# MCU.net
KiCad netlist of a schematic drawn in Altium Designer
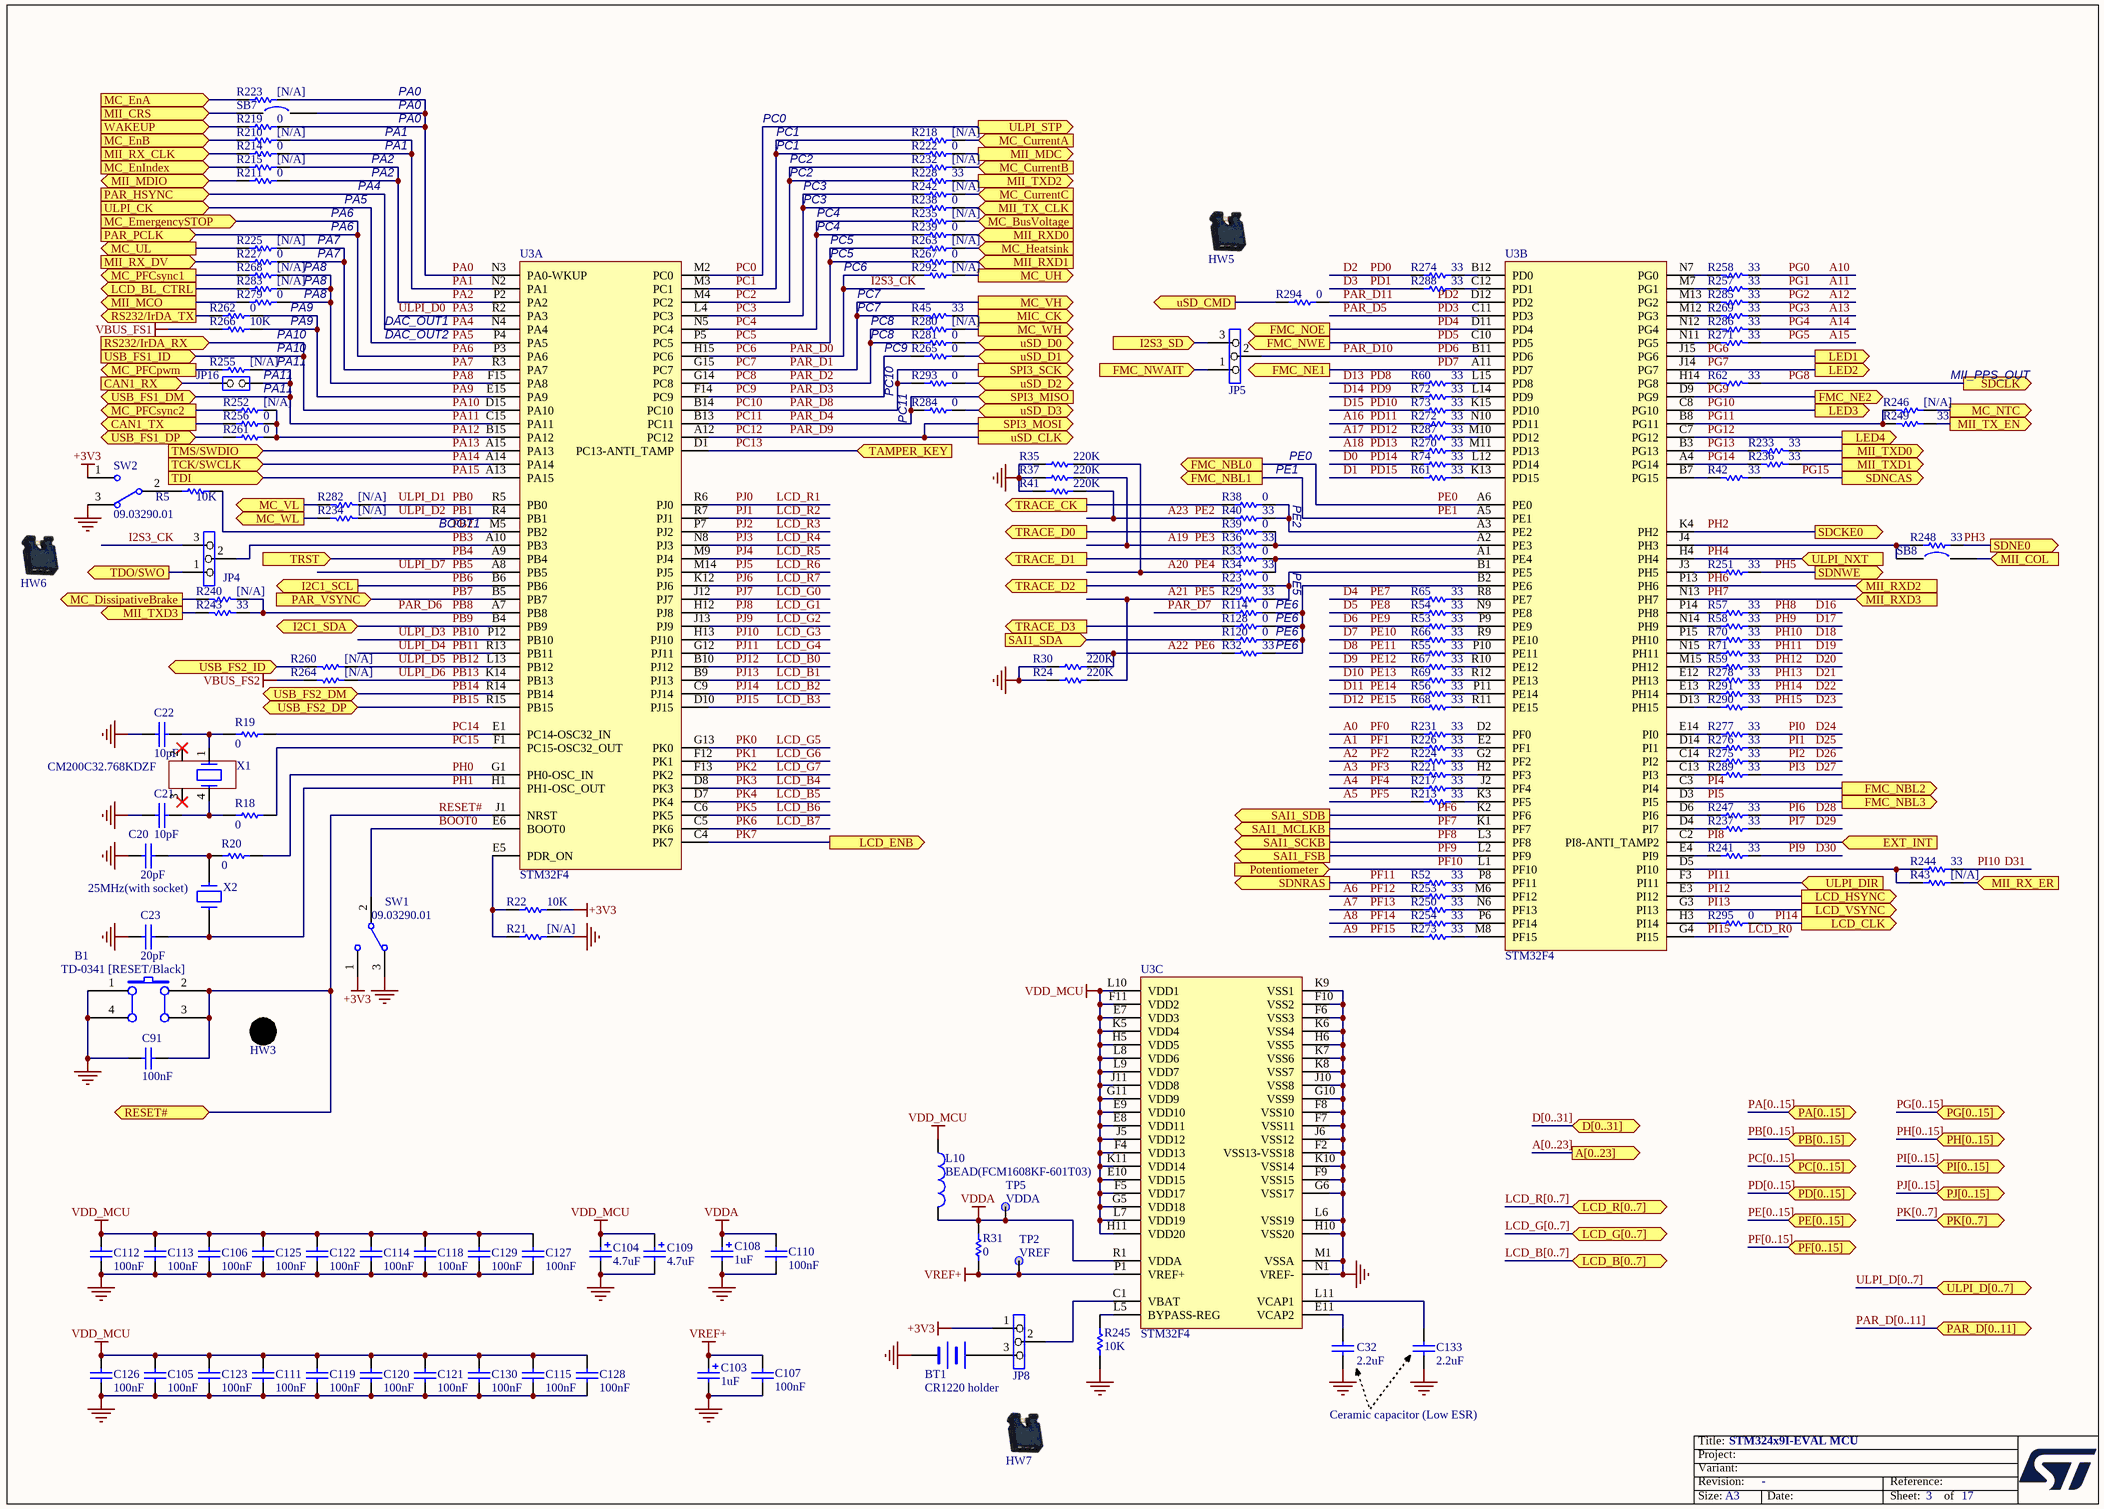
[diagram p0: MCU.SchDoc]

(export (version "E")
  (design (tool "Eeschema 10.0.6"))
  (components
    (comp (ref "B1")
      (value "TD-0341 [RESET/Black]")
      (footprint "PB10")
      (description "SE PUSHBUTTON")
      (libsource (lib "Documents") (part "SW PUSHBUTTON"))
    )
    (comp (ref "BT1")
      (value "CR1220 holder")
      (footprint "BAT_2SM_CR1220")
      (description "Battery")
      (libsource (lib "*") (part "BATTERY"))
    )
    (comp (ref "C20")
      (value "20pF")
      (footprint "0603C")
      (description "Capacitor")
      (libsource (lib "") (part "CAP_1"))
    )
    (comp (ref "C21")
      (value "10pF")
      (footprint "0603C")
      (description "Capacitor")
      (libsource (lib "*") (part "CAP"))
    )
    (comp (ref "C22")
      (value "10pF")
      (footprint "0603C")
      (description "Capacitor")
      (libsource (lib "*") (part "CAP"))
    )
    (comp (ref "C23")
      (value "20pF")
      (footprint "0603C")
      (description "Capacitor")
      (libsource (lib "") (part "CAP_1"))
    )
    (comp (ref "C32")
      (value "2.2uF")
      (footprint "1206C")
      (description "Capacitor")
      (fields (field (name "PUBLISHER") "Altium Limited"))
      (libsource (lib "Miscellaneous Devices") (part "Cap"))
    )
    (comp (ref "C91")
      (value "100nF")
      (footprint "0603C")
      (description "Capacitor")
      (fields (field (name "PUBLISHER") "Altium Limited"))
      (libsource (lib "Miscellaneous Devices") (part "CAP"))
    )
    (comp (ref "C103")
      (value "1uF")
      (footprint "TAN-A")
      (description "Polarized Capacitor (Radial)")
      (fields (field (name "PUBLISHER") "Altium Limited"))
      (libsource (lib "Miscellaneous Devices") (part "Cap Pol1"))
    )
    (comp (ref "C104")
      (value "4.7uF")
      (footprint "TAN-A")
      (description "Polarized Capacitor (Radial)")
      (fields (field (name "PUBLISHER") "Altium Limited"))
      (libsource (lib "Miscellaneous Devices") (part "Cap Pol1"))
    )
    (comp (ref "C105")
      (value "100nF")
      (footprint "0402C")
      (description "Capacitor")
      (fields (field (name "PUBLISHER") "Altium Limited"))
      (libsource (lib "Miscellaneous Devices") (part "CAP"))
    )
    (comp (ref "C106")
      (value "100nF")
      (footprint "0402C")
      (description "Capacitor")
      (fields (field (name "PUBLISHER") "Altium Limited"))
      (libsource (lib "Miscellaneous Devices") (part "CAP"))
    )
    (comp (ref "C107")
      (value "100nF")
      (footprint "0402C")
      (description "Capacitor")
      (fields (field (name "PUBLISHER") "Altium Limited"))
      (libsource (lib "Miscellaneous Devices") (part "Cap"))
    )
    (comp (ref "C108")
      (value "1uF")
      (footprint "TAN-A")
      (description "Polarized Capacitor (Radial)")
      (fields (field (name "PUBLISHER") "Altium Limited"))
      (libsource (lib "Miscellaneous Devices") (part "Cap Pol1"))
    )
    (comp (ref "C109")
      (value "4.7uF")
      (footprint "TAN-A")
      (description "Polarized Capacitor (Radial)")
      (fields (field (name "PUBLISHER") "Altium Limited"))
      (libsource (lib "Miscellaneous Devices") (part "Cap Pol1"))
    )
    (comp (ref "C110")
      (value "100nF")
      (footprint "0402C")
      (description "Capacitor")
      (fields (field (name "PUBLISHER") "Altium Limited"))
      (libsource (lib "Miscellaneous Devices") (part "Cap"))
    )
    (comp (ref "C111")
      (value "100nF")
      (footprint "0402C")
      (description "Capacitor")
      (fields (field (name "PUBLISHER") "Altium Limited"))
      (libsource (lib "Miscellaneous Devices") (part "CAP"))
    )
    (comp (ref "C112")
      (value "100nF")
      (footprint "0402C")
      (description "Capacitor")
      (fields (field (name "PUBLISHER") "Altium Limited"))
      (libsource (lib "Miscellaneous Devices") (part "CAP"))
    )
    (comp (ref "C113")
      (value "100nF")
      (footprint "0402C")
      (description "Capacitor")
      (fields (field (name "PUBLISHER") "Altium Limited"))
      (libsource (lib "Miscellaneous Devices") (part "CAP"))
    )
    (comp (ref "C114")
      (value "100nF")
      (footprint "0402C")
      (description "Capacitor")
      (fields (field (name "PUBLISHER") "Altium Limited"))
      (libsource (lib "Miscellaneous Devices") (part "CAP"))
    )
    (comp (ref "C115")
      (value "100nF")
      (footprint "0402C")
      (description "Capacitor")
      (fields (field (name "PUBLISHER") "Altium Limited"))
      (libsource (lib "Miscellaneous Devices") (part "CAP"))
    )
    (comp (ref "C118")
      (value "100nF")
      (footprint "0402C")
      (description "Capacitor")
      (fields (field (name "PUBLISHER") "Altium Limited"))
      (libsource (lib "Miscellaneous Devices") (part "CAP"))
    )
    (comp (ref "C119")
      (value "100nF")
      (footprint "0402C")
      (description "Capacitor")
      (fields (field (name "PUBLISHER") "Altium Limited"))
      (libsource (lib "Miscellaneous Devices") (part "CAP"))
    )
    (comp (ref "C120")
      (value "100nF")
      (footprint "0402C")
      (description "Capacitor")
      (fields (field (name "PUBLISHER") "Altium Limited"))
      (libsource (lib "Miscellaneous Devices") (part "CAP"))
    )
    (comp (ref "C121")
      (value "100nF")
      (footprint "0402C")
      (description "Capacitor")
      (fields (field (name "PUBLISHER") "Altium Limited"))
      (libsource (lib "Miscellaneous Devices") (part "CAP"))
    )
    (comp (ref "C122")
      (value "100nF")
      (footprint "0402C")
      (description "Capacitor")
      (fields (field (name "PUBLISHER") "Altium Limited"))
      (libsource (lib "Miscellaneous Devices") (part "CAP"))
    )
    (comp (ref "C123")
      (value "100nF")
      (footprint "0402C")
      (description "Capacitor")
      (fields (field (name "PUBLISHER") "Altium Limited"))
      (libsource (lib "Miscellaneous Devices") (part "CAP"))
    )
    (comp (ref "C125")
      (value "100nF")
      (footprint "0402C")
      (description "Capacitor")
      (fields (field (name "PUBLISHER") "Altium Limited"))
      (libsource (lib "Miscellaneous Devices") (part "CAP"))
    )
    (comp (ref "C126")
      (value "100nF")
      (footprint "0402C")
      (description "Capacitor")
      (fields (field (name "PUBLISHER") "Altium Limited"))
      (libsource (lib "Miscellaneous Devices") (part "CAP"))
    )
    (comp (ref "C127")
      (value "100nF")
      (footprint "0402C")
      (description "Capacitor")
      (fields (field (name "PUBLISHER") "Altium Limited"))
      (libsource (lib "Miscellaneous Devices") (part "CAP"))
    )
    (comp (ref "C128")
      (value "100nF")
      (footprint "0402C")
      (description "Capacitor")
      (fields (field (name "PUBLISHER") "Altium Limited"))
      (libsource (lib "Miscellaneous Devices") (part "CAP"))
    )
    (comp (ref "C129")
      (value "100nF")
      (footprint "0402C")
      (description "Capacitor")
      (fields (field (name "PUBLISHER") "Altium Limited"))
      (libsource (lib "Miscellaneous Devices") (part "CAP"))
    )
    (comp (ref "C130")
      (value "100nF")
      (footprint "0402C")
      (description "Capacitor")
      (fields (field (name "PUBLISHER") "Altium Limited"))
      (libsource (lib "Miscellaneous Devices") (part "CAP"))
    )
    (comp (ref "C133")
      (value "2.2uF")
      (footprint "1206C")
      (description "Capacitor")
      (fields (field (name "PUBLISHER") "Altium Limited"))
      (libsource (lib "Miscellaneous Devices") (part "Cap"))
    )
    (comp (ref "HW3") (value "BUTTON_HAT_BLACK") (libsource (lib "mb1045") (part "BUTTON_HAT_BLACK")))
    (comp (ref "HW5") (value "JUMPER_OPEN") (libsource (lib "mb1045") (part "JUMPER_OPEN")))
    (comp (ref "HW6") (value "JUMPER_OPEN") (libsource (lib "mb1045") (part "JUMPER_OPEN")))
    (comp (ref "HW7") (value "JUMPER_OPEN") (libsource (lib "mb1045") (part "JUMPER_OPEN")))
    (comp (ref "JP4") (value "~") (footprint "SIP3") (libsource (lib "") (part "Jumper3_1")))
    (comp (ref "JP5") (value "~") (footprint "SIP3") (libsource (lib "") (part "Jumper3_1")))
    (comp (ref "JP8") (value "~") (footprint "SIP3") (libsource (lib "STR910_SCHLIB") (part "Jumper3")))
    (comp (ref "JP16") (value "~") (footprint "SIP2") (libsource (lib "*") (part "JP2")))
    (comp (ref "L10")
      (value "BEAD(FCM1608KF-601T03)")
      (footprint "0603L")
      (description "Inductor")
      (fields (field (name "PUBLISHER") "Altium Limited"))
      (libsource (lib "Miscellaneous Devices") (part "Inductor"))
    )
    (comp (ref "R5")
      (value "10K")
      (footprint "0603R")
      (description "Resistor")
      (fields (field (name "PUBLISHER") "Altium Limited"))
      (libsource (lib "Miscellaneous Devices") (part "Res1"))
    )
    (comp (ref "R18")
      (value "0")
      (footprint "0603R")
      (description "Resistor")
      (fields (field (name "PUBLISHER") "Altium Limited"))
      (libsource (lib "") (part "Res1_1"))
    )
    (comp (ref "R19")
      (value "0")
      (footprint "0603R")
      (description "Resistor")
      (fields (field (name "PUBLISHER") "Altium Limited"))
      (libsource (lib "") (part "Res1_1"))
    )
    (comp (ref "R20")
      (value "0")
      (footprint "0603R")
      (description "Resistor")
      (fields (field (name "PUBLISHER") "Altium Limited"))
      (libsource (lib "Miscellaneous Devices") (part "Res1"))
    )
    (comp (ref "R21")
      (value "[N/A]")
      (footprint "0603R")
      (description "Resistor")
      (fields (field (name "PUBLISHER") "Altium Limited"))
      (libsource (lib "Miscellaneous Devices") (part "Res1"))
    )
    (comp (ref "R22")
      (value "10K")
      (footprint "0603R")
      (description "Resistor")
      (fields (field (name "PUBLISHER") "Altium Limited"))
      (libsource (lib "Miscellaneous Devices") (part "Res1"))
    )
    (comp (ref "R23")
      (value "0")
      (footprint "0603R")
      (description "Resistor")
      (fields (field (name "PUBLISHER") "Altium Limited"))
      (libsource (lib "Miscellaneous Devices") (part "Res1"))
    )
    (comp (ref "R24")
      (value "220K")
      (footprint "0603R")
      (description "Resistor")
      (fields (field (name "PUBLISHER") "Altium Limited"))
      (libsource (lib "Miscellaneous Devices") (part "res1"))
    )
    (comp (ref "R29")
      (value "33")
      (footprint "0402R")
      (description "Resistor")
      (fields (field (name "PUBLISHER") "Altium Limited"))
      (libsource (lib "Miscellaneous Devices") (part "Res1"))
    )
    (comp (ref "R30")
      (value "220K")
      (footprint "0603R")
      (description "Resistor")
      (fields (field (name "PUBLISHER") "Altium Limited"))
      (libsource (lib "Miscellaneous Devices") (part "res1"))
    )
    (comp (ref "R31")
      (value "0")
      (footprint "0603R")
      (description "Resistor")
      (fields (field (name "PUBLISHER") "Altium Limited"))
      (libsource (lib "Miscellaneous Devices") (part "Res1"))
    )
    (comp (ref "R32")
      (value "33")
      (footprint "0402R")
      (description "Resistor")
      (fields (field (name "PUBLISHER") "Altium Limited"))
      (libsource (lib "Miscellaneous Devices") (part "Res1"))
    )
    (comp (ref "R33")
      (value "0")
      (footprint "0603R")
      (description "Resistor")
      (fields (field (name "PUBLISHER") "Altium Limited"))
      (libsource (lib "Miscellaneous Devices") (part "Res1"))
    )
    (comp (ref "R34")
      (value "33")
      (footprint "0402R")
      (description "Resistor")
      (fields (field (name "PUBLISHER") "Altium Limited"))
      (libsource (lib "Miscellaneous Devices") (part "Res1"))
    )
    (comp (ref "R35")
      (value "220K")
      (footprint "0603R")
      (description "Resistor")
      (fields (field (name "PUBLISHER") "Altium Limited"))
      (libsource (lib "Miscellaneous Devices") (part "res1"))
    )
    (comp (ref "R36")
      (value "33")
      (footprint "0402R")
      (description "Resistor")
      (fields (field (name "PUBLISHER") "Altium Limited"))
      (libsource (lib "Miscellaneous Devices") (part "Res1"))
    )
    (comp (ref "R37")
      (value "220K")
      (footprint "0603R")
      (description "Resistor")
      (fields (field (name "PUBLISHER") "Altium Limited"))
      (libsource (lib "Miscellaneous Devices") (part "res1"))
    )
    (comp (ref "R38")
      (value "0")
      (footprint "0603R")
      (description "Resistor")
      (fields (field (name "PUBLISHER") "Altium Limited"))
      (libsource (lib "Miscellaneous Devices") (part "Res1"))
    )
    (comp (ref "R39")
      (value "0")
      (footprint "0603R")
      (description "Resistor")
      (fields (field (name "PUBLISHER") "Altium Limited"))
      (libsource (lib "Miscellaneous Devices") (part "Res1"))
    )
    (comp (ref "R40")
      (value "33")
      (footprint "0402R")
      (description "Resistor")
      (fields (field (name "PUBLISHER") "Altium Limited"))
      (libsource (lib "Miscellaneous Devices") (part "Res1"))
    )
    (comp (ref "R41")
      (value "220K")
      (footprint "0603R")
      (description "Resistor")
      (fields (field (name "PUBLISHER") "Altium Limited"))
      (libsource (lib "Miscellaneous Devices") (part "res1"))
    )
    (comp (ref "R42")
      (value "33")
      (footprint "0402R")
      (description "Resistor")
      (fields (field (name "PUBLISHER") "Altium Limited"))
      (libsource (lib "Miscellaneous Devices") (part "Res1"))
    )
    (comp (ref "R43")
      (value "[N/A]")
      (footprint "0603R")
      (description "Resistor")
      (fields (field (name "PUBLISHER") "Altium Limited"))
      (libsource (lib "Miscellaneous Devices") (part "Res1"))
    )
    (comp (ref "R45")
      (value "33")
      (footprint "0603R")
      (description "Resistor")
      (fields (field (name "PUBLISHER") "Altium Limited"))
      (libsource (lib "Miscellaneous Devices") (part "Res1"))
    )
    (comp (ref "R52")
      (value "33")
      (footprint "0402R")
      (description "Resistor")
      (fields (field (name "PUBLISHER") "Altium Limited"))
      (libsource (lib "Miscellaneous Devices") (part "Res1"))
    )
    (comp (ref "R53")
      (value "33")
      (footprint "0402R")
      (description "Resistor")
      (fields (field (name "PUBLISHER") "Altium Limited"))
      (libsource (lib "Miscellaneous Devices") (part "Res1"))
    )
    (comp (ref "R54")
      (value "33")
      (footprint "0402R")
      (description "Resistor")
      (fields (field (name "PUBLISHER") "Altium Limited"))
      (libsource (lib "Miscellaneous Devices") (part "Res1"))
    )
    (comp (ref "R55")
      (value "33")
      (footprint "0402R")
      (description "Resistor")
      (fields (field (name "PUBLISHER") "Altium Limited"))
      (libsource (lib "Miscellaneous Devices") (part "Res1"))
    )
    (comp (ref "R56")
      (value "33")
      (footprint "0402R")
      (description "Resistor")
      (fields (field (name "PUBLISHER") "Altium Limited"))
      (libsource (lib "Miscellaneous Devices") (part "Res1"))
    )
    (comp (ref "R57")
      (value "33")
      (footprint "0402R")
      (description "Resistor")
      (fields (field (name "PUBLISHER") "Altium Limited"))
      (libsource (lib "Miscellaneous Devices") (part "Res1"))
    )
    (comp (ref "R58")
      (value "33")
      (footprint "0402R")
      (description "Resistor")
      (fields (field (name "PUBLISHER") "Altium Limited"))
      (libsource (lib "Miscellaneous Devices") (part "Res1"))
    )
    (comp (ref "R59")
      (value "33")
      (footprint "0402R")
      (description "Resistor")
      (fields (field (name "PUBLISHER") "Altium Limited"))
      (libsource (lib "Miscellaneous Devices") (part "Res1"))
    )
    (comp (ref "R60")
      (value "33")
      (footprint "0402R")
      (description "Resistor")
      (fields (field (name "PUBLISHER") "Altium Limited"))
      (libsource (lib "Miscellaneous Devices") (part "Res1"))
    )
    (comp (ref "R61")
      (value "33")
      (footprint "0402R")
      (description "Resistor")
      (fields (field (name "PUBLISHER") "Altium Limited"))
      (libsource (lib "Miscellaneous Devices") (part "Res1"))
    )
    (comp (ref "R62")
      (value "33")
      (footprint "0402R")
      (description "Resistor")
      (fields (field (name "PUBLISHER") "Altium Limited"))
      (libsource (lib "Miscellaneous Devices") (part "Res1"))
    )
    (comp (ref "R65")
      (value "33")
      (footprint "0402R")
      (description "Resistor")
      (fields (field (name "PUBLISHER") "Altium Limited"))
      (libsource (lib "Miscellaneous Devices") (part "Res1"))
    )
    (comp (ref "R66")
      (value "33")
      (footprint "0402R")
      (description "Resistor")
      (fields (field (name "PUBLISHER") "Altium Limited"))
      (libsource (lib "Miscellaneous Devices") (part "Res1"))
    )
    (comp (ref "R67")
      (value "33")
      (footprint "0402R")
      (description "Resistor")
      (fields (field (name "PUBLISHER") "Altium Limited"))
      (libsource (lib "Miscellaneous Devices") (part "Res1"))
    )
    (comp (ref "R68")
      (value "33")
      (footprint "0402R")
      (description "Resistor")
      (fields (field (name "PUBLISHER") "Altium Limited"))
      (libsource (lib "Miscellaneous Devices") (part "Res1"))
    )
    (comp (ref "R69")
      (value "33")
      (footprint "0402R")
      (description "Resistor")
      (fields (field (name "PUBLISHER") "Altium Limited"))
      (libsource (lib "Miscellaneous Devices") (part "Res1"))
    )
    (comp (ref "R70")
      (value "33")
      (footprint "0402R")
      (description "Resistor")
      (fields (field (name "PUBLISHER") "Altium Limited"))
      (libsource (lib "Miscellaneous Devices") (part "Res1"))
    )
    (comp (ref "R71")
      (value "33")
      (footprint "0402R")
      (description "Resistor")
      (fields (field (name "PUBLISHER") "Altium Limited"))
      (libsource (lib "Miscellaneous Devices") (part "Res1"))
    )
    (comp (ref "R72")
      (value "33")
      (footprint "0402R")
      (description "Resistor")
      (fields (field (name "PUBLISHER") "Altium Limited"))
      (libsource (lib "Miscellaneous Devices") (part "Res1"))
    )
    (comp (ref "R73")
      (value "33")
      (footprint "0402R")
      (description "Resistor")
      (fields (field (name "PUBLISHER") "Altium Limited"))
      (libsource (lib "Miscellaneous Devices") (part "Res1"))
    )
    (comp (ref "R74")
      (value "33")
      (footprint "0402R")
      (description "Resistor")
      (fields (field (name "PUBLISHER") "Altium Limited"))
      (libsource (lib "Miscellaneous Devices") (part "Res1"))
    )
    (comp (ref "R114")
      (value "0")
      (footprint "0603R")
      (description "Resistor")
      (fields (field (name "PUBLISHER") "Altium Limited"))
      (libsource (lib "Miscellaneous Devices") (part "Res1"))
    )
    (comp (ref "R120")
      (value "0")
      (footprint "0603R")
      (description "Resistor")
      (fields (field (name "PUBLISHER") "Altium Limited"))
      (libsource (lib "Miscellaneous Devices") (part "Res1"))
    )
    (comp (ref "R128")
      (value "0")
      (footprint "0603R")
      (description "Resistor")
      (fields (field (name "PUBLISHER") "Altium Limited"))
      (libsource (lib "Miscellaneous Devices") (part "Res1"))
    )
    (comp (ref "R210")
      (value "[N/A]")
      (footprint "0603R")
      (description "Resistor")
      (fields (field (name "PUBLISHER") "Altium Limited"))
      (libsource (lib "Miscellaneous Devices") (part "Res1"))
    )
    (comp (ref "R211")
      (value "0")
      (footprint "0603R")
      (description "Resistor")
      (fields (field (name "PUBLISHER") "Altium Limited"))
      (libsource (lib "Miscellaneous Devices") (part "Res1"))
    )
    (comp (ref "R213")
      (value "33")
      (footprint "0402R")
      (description "Resistor")
      (fields (field (name "PUBLISHER") "Altium Limited"))
      (libsource (lib "Miscellaneous Devices") (part "Res1"))
    )
    (comp (ref "R214")
      (value "0")
      (footprint "0603R")
      (description "Resistor")
      (fields (field (name "PUBLISHER") "Altium Limited"))
      (libsource (lib "Miscellaneous Devices") (part "Res1"))
    )
    (comp (ref "R215")
      (value "[N/A]")
      (footprint "0603R")
      (description "Resistor")
      (fields (field (name "PUBLISHER") "Altium Limited"))
      (libsource (lib "Miscellaneous Devices") (part "Res1"))
    )
    (comp (ref "R217")
      (value "33")
      (footprint "0402R")
      (description "Resistor")
      (fields (field (name "PUBLISHER") "Altium Limited"))
      (libsource (lib "Miscellaneous Devices") (part "Res1"))
    )
    (comp (ref "R218")
      (value "[N/A]")
      (footprint "0603R")
      (description "Resistor")
      (fields (field (name "PUBLISHER") "Altium Limited"))
      (libsource (lib "Miscellaneous Devices") (part "Res1"))
    )
    (comp (ref "R219")
      (value "0")
      (footprint "0603R")
      (description "Resistor")
      (fields (field (name "PUBLISHER") "Altium Limited"))
      (libsource (lib "Miscellaneous Devices") (part "Res1"))
    )
    (comp (ref "R221")
      (value "33")
      (footprint "0402R")
      (description "Resistor")
      (fields (field (name "PUBLISHER") "Altium Limited"))
      (libsource (lib "Miscellaneous Devices") (part "Res1"))
    )
    (comp (ref "R222")
      (value "0")
      (footprint "0603R")
      (description "Resistor")
      (fields (field (name "PUBLISHER") "Altium Limited"))
      (libsource (lib "Miscellaneous Devices") (part "Res1"))
    )
    (comp (ref "R223")
      (value "[N/A]")
      (footprint "0603R")
      (description "Resistor")
      (fields (field (name "PUBLISHER") "Altium Limited"))
      (libsource (lib "Miscellaneous Devices") (part "Res1"))
    )
    (comp (ref "R224")
      (value "33")
      (footprint "0402R")
      (description "Resistor")
      (fields (field (name "PUBLISHER") "Altium Limited"))
      (libsource (lib "Miscellaneous Devices") (part "Res1"))
    )
    (comp (ref "R225")
      (value "[N/A]")
      (footprint "0603R")
      (description "Resistor")
      (fields (field (name "PUBLISHER") "Altium Limited"))
      (libsource (lib "Miscellaneous Devices") (part "Res1"))
    )
    (comp (ref "R226")
      (value "33")
      (footprint "0402R")
      (description "Resistor")
      (fields (field (name "PUBLISHER") "Altium Limited"))
      (libsource (lib "Miscellaneous Devices") (part "Res1"))
    )
    (comp (ref "R227")
      (value "0")
      (footprint "0603R")
      (description "Resistor")
      (fields (field (name "PUBLISHER") "Altium Limited"))
      (libsource (lib "Miscellaneous Devices") (part "Res1"))
    )
    (comp (ref "R228")
      (value "33")
      (footprint "0603R")
      (description "Resistor")
      (fields (field (name "PUBLISHER") "Altium Limited"))
      (libsource (lib "Miscellaneous Devices") (part "Res1"))
    )
    (comp (ref "R231")
      (value "33")
      (footprint "0402R")
      (description "Resistor")
      (fields (field (name "PUBLISHER") "Altium Limited"))
      (libsource (lib "Miscellaneous Devices") (part "Res1"))
    )
    (comp (ref "R232")
      (value "[N/A]")
      (footprint "0603R")
      (description "Resistor")
      (fields (field (name "PUBLISHER") "Altium Limited"))
      (libsource (lib "Miscellaneous Devices") (part "Res1"))
    )
    (comp (ref "R233")
      (value "33")
      (footprint "0603R")
      (description "Resistor")
      (fields (field (name "PUBLISHER") "Altium Limited"))
      (libsource (lib "Miscellaneous Devices") (part "Res1"))
    )
    (comp (ref "R234")
      (value "[N/A]")
      (footprint "0603R")
      (description "Resistor")
      (fields (field (name "PUBLISHER") "Altium Limited"))
      (libsource (lib "Miscellaneous Devices") (part "Res1"))
    )
    (comp (ref "R235")
      (value "[N/A]")
      (footprint "0603R")
      (description "Resistor")
      (fields (field (name "PUBLISHER") "Altium Limited"))
      (libsource (lib "Miscellaneous Devices") (part "Res1"))
    )
    (comp (ref "R236")
      (value "33")
      (footprint "0603R")
      (description "Resistor")
      (fields (field (name "PUBLISHER") "Altium Limited"))
      (libsource (lib "Miscellaneous Devices") (part "Res1"))
    )
    (comp (ref "R237")
      (value "33")
      (footprint "0402R")
      (description "Resistor")
      (fields (field (name "PUBLISHER") "Altium Limited"))
      (libsource (lib "Miscellaneous Devices") (part "Res1"))
    )
    (comp (ref "R238")
      (value "0")
      (footprint "0603R")
      (description "Resistor")
      (fields (field (name "PUBLISHER") "Altium Limited"))
      (libsource (lib "Miscellaneous Devices") (part "Res1"))
    )
    (comp (ref "R239")
      (value "0")
      (footprint "0603R")
      (description "Resistor")
      (fields (field (name "PUBLISHER") "Altium Limited"))
      (libsource (lib "Miscellaneous Devices") (part "Res1"))
    )
    (comp (ref "R240")
      (value "[N/A]")
      (footprint "0603R")
      (description "Resistor")
      (fields (field (name "PUBLISHER") "Altium Limited"))
      (libsource (lib "Miscellaneous Devices") (part "Res1"))
    )
    (comp (ref "R241")
      (value "33")
      (footprint "0402R")
      (description "Resistor")
      (fields (field (name "PUBLISHER") "Altium Limited"))
      (libsource (lib "Miscellaneous Devices") (part "Res1"))
    )
    (comp (ref "R242")
      (value "[N/A]")
      (footprint "0603R")
      (description "Resistor")
      (fields (field (name "PUBLISHER") "Altium Limited"))
      (libsource (lib "Miscellaneous Devices") (part "Res1"))
    )
    (comp (ref "R243")
      (value "33")
      (footprint "0603R")
      (description "Resistor")
      (fields (field (name "PUBLISHER") "Altium Limited"))
      (libsource (lib "Miscellaneous Devices") (part "Res1"))
    )
    (comp (ref "R244")
      (value "33")
      (footprint "0402R")
      (description "Resistor")
      (fields (field (name "PUBLISHER") "Altium Limited"))
      (libsource (lib "Miscellaneous Devices") (part "Res1"))
    )
    (comp (ref "R245")
      (value "10K")
      (footprint "0603R")
      (description "Resistor")
      (fields (field (name "PUBLISHER") "Altium Limited"))
      (libsource (lib "Miscellaneous Devices") (part "Res1"))
    )
    (comp (ref "R246")
      (value "[N/A]")
      (footprint "0603R")
      (description "Resistor")
      (fields (field (name "PUBLISHER") "Altium Limited"))
      (libsource (lib "Miscellaneous Devices") (part "Res1"))
    )
    (comp (ref "R247")
      (value "33")
      (footprint "0402R")
      (description "Resistor")
      (fields (field (name "PUBLISHER") "Altium Limited"))
      (libsource (lib "Miscellaneous Devices") (part "Res1"))
    )
    (comp (ref "R248")
      (value "33")
      (footprint "0402R")
      (description "Resistor")
      (fields (field (name "PUBLISHER") "Altium Limited"))
      (libsource (lib "Miscellaneous Devices") (part "Res1"))
    )
    (comp (ref "R249")
      (value "33")
      (footprint "0603R")
      (description "Resistor")
      (fields (field (name "PUBLISHER") "Altium Limited"))
      (libsource (lib "Miscellaneous Devices") (part "Res1"))
    )
    (comp (ref "R250")
      (value "33")
      (footprint "0402R")
      (description "Resistor")
      (fields (field (name "PUBLISHER") "Altium Limited"))
      (libsource (lib "Miscellaneous Devices") (part "Res1"))
    )
    (comp (ref "R251")
      (value "33")
      (footprint "0402R")
      (description "Resistor")
      (fields (field (name "PUBLISHER") "Altium Limited"))
      (libsource (lib "Miscellaneous Devices") (part "Res1"))
    )
    (comp (ref "R252")
      (value "[N/A]")
      (footprint "0603R")
      (description "Resistor")
      (fields (field (name "PUBLISHER") "Altium Limited"))
      (libsource (lib "Miscellaneous Devices") (part "Res1"))
    )
    (comp (ref "R253")
      (value "33")
      (footprint "0402R")
      (description "Resistor")
      (fields (field (name "PUBLISHER") "Altium Limited"))
      (libsource (lib "Miscellaneous Devices") (part "Res1"))
    )
    (comp (ref "R254")
      (value "33")
      (footprint "0402R")
      (description "Resistor")
      (fields (field (name "PUBLISHER") "Altium Limited"))
      (libsource (lib "Miscellaneous Devices") (part "Res1"))
    )
    (comp (ref "R255")
      (value "[N/A]")
      (footprint "0603R")
      (description "Resistor")
      (fields (field (name "PUBLISHER") "Altium Limited"))
      (libsource (lib "Miscellaneous Devices") (part "Res1"))
    )
    (comp (ref "R256")
      (value "0")
      (footprint "0603R")
      (description "Resistor")
      (fields (field (name "PUBLISHER") "Altium Limited"))
      (libsource (lib "Miscellaneous Devices") (part "Res1"))
    )
    (comp (ref "R257")
      (value "33")
      (footprint "0402R")
      (description "Resistor")
      (fields (field (name "PUBLISHER") "Altium Limited"))
      (libsource (lib "Miscellaneous Devices") (part "Res1"))
    )
    (comp (ref "R258")
      (value "33")
      (footprint "0402R")
      (description "Resistor")
      (fields (field (name "PUBLISHER") "Altium Limited"))
      (libsource (lib "Miscellaneous Devices") (part "Res1"))
    )
    (comp (ref "R260")
      (value "[N/A]")
      (footprint "0603R")
      (description "Resistor")
      (fields (field (name "PUBLISHER") "Altium Limited"))
      (libsource (lib "Miscellaneous Devices") (part "Res1"))
    )
    (comp (ref "R261")
      (value "0")
      (footprint "0603R")
      (description "Resistor")
      (fields (field (name "PUBLISHER") "Altium Limited"))
      (libsource (lib "Miscellaneous Devices") (part "Res1"))
    )
    (comp (ref "R262")
      (value "0")
      (footprint "0603R")
      (description "Resistor")
      (fields (field (name "PUBLISHER") "Altium Limited"))
      (libsource (lib "Miscellaneous Devices") (part "Res1"))
    )
    (comp (ref "R263")
      (value "[N/A]")
      (footprint "0603R")
      (description "Resistor")
      (fields (field (name "PUBLISHER") "Altium Limited"))
      (libsource (lib "Miscellaneous Devices") (part "Res1"))
    )
    (comp (ref "R264")
      (value "[N/A]")
      (footprint "0603R")
      (description "Resistor")
      (fields (field (name "PUBLISHER") "Altium Limited"))
      (libsource (lib "Miscellaneous Devices") (part "Res1"))
    )
    (comp (ref "R265")
      (value "0")
      (footprint "0603R")
      (description "Resistor")
      (fields (field (name "PUBLISHER") "Altium Limited"))
      (libsource (lib "Miscellaneous Devices") (part "Res1"))
    )
    (comp (ref "R266")
      (value "10K")
      (footprint "0603R")
      (description "Resistor")
      (fields (field (name "PUBLISHER") "Altium Limited"))
      (libsource (lib "Miscellaneous Devices") (part "res1"))
    )
    (comp (ref "R267")
      (value "0")
      (footprint "0603R")
      (description "Resistor")
      (fields (field (name "PUBLISHER") "Altium Limited"))
      (libsource (lib "Miscellaneous Devices") (part "Res1"))
    )
    (comp (ref "R268")
      (value "[N/A]")
      (footprint "0603R")
      (description "Resistor")
      (fields (field (name "PUBLISHER") "Altium Limited"))
      (libsource (lib "Miscellaneous Devices") (part "Res1"))
    )
    (comp (ref "R269")
      (value "33")
      (footprint "0402R")
      (description "Resistor")
      (fields (field (name "PUBLISHER") "Altium Limited"))
      (libsource (lib "Miscellaneous Devices") (part "Res1"))
    )
    (comp (ref "R270")
      (value "33")
      (footprint "0402R")
      (description "Resistor")
      (fields (field (name "PUBLISHER") "Altium Limited"))
      (libsource (lib "Miscellaneous Devices") (part "Res1"))
    )
    (comp (ref "R271")
      (value "33")
      (footprint "0402R")
      (description "Resistor")
      (fields (field (name "PUBLISHER") "Altium Limited"))
      (libsource (lib "Miscellaneous Devices") (part "Res1"))
    )
    (comp (ref "R272")
      (value "33")
      (footprint "0402R")
      (description "Resistor")
      (fields (field (name "PUBLISHER") "Altium Limited"))
      (libsource (lib "Miscellaneous Devices") (part "Res1"))
    )
    (comp (ref "R273")
      (value "33")
      (footprint "0402R")
      (description "Resistor")
      (fields (field (name "PUBLISHER") "Altium Limited"))
      (libsource (lib "Miscellaneous Devices") (part "Res1"))
    )
    (comp (ref "R274")
      (value "33")
      (footprint "0402R")
      (description "Resistor")
      (fields (field (name "PUBLISHER") "Altium Limited"))
      (libsource (lib "Miscellaneous Devices") (part "Res1"))
    )
    (comp (ref "R275")
      (value "33")
      (footprint "0402R")
      (description "Resistor")
      (fields (field (name "PUBLISHER") "Altium Limited"))
      (libsource (lib "Miscellaneous Devices") (part "Res1"))
    )
    (comp (ref "R276")
      (value "33")
      (footprint "0402R")
      (description "Resistor")
      (fields (field (name "PUBLISHER") "Altium Limited"))
      (libsource (lib "Miscellaneous Devices") (part "Res1"))
    )
    (comp (ref "R277")
      (value "33")
      (footprint "0402R")
      (description "Resistor")
      (fields (field (name "PUBLISHER") "Altium Limited"))
      (libsource (lib "Miscellaneous Devices") (part "Res1"))
    )
    (comp (ref "R278")
      (value "33")
      (footprint "0402R")
      (description "Resistor")
      (fields (field (name "PUBLISHER") "Altium Limited"))
      (libsource (lib "Miscellaneous Devices") (part "Res1"))
    )
    (comp (ref "R279")
      (value "0")
      (footprint "0603R")
      (description "Resistor")
      (fields (field (name "PUBLISHER") "Altium Limited"))
      (libsource (lib "Miscellaneous Devices") (part "Res1"))
    )
    (comp (ref "R280")
      (value "[N/A]")
      (footprint "0603R")
      (description "Resistor")
      (fields (field (name "PUBLISHER") "Altium Limited"))
      (libsource (lib "Miscellaneous Devices") (part "Res1"))
    )
    (comp (ref "R281")
      (value "0")
      (footprint "0603R")
      (description "Resistor")
      (fields (field (name "PUBLISHER") "Altium Limited"))
      (libsource (lib "Miscellaneous Devices") (part "Res1"))
    )
    (comp (ref "R282")
      (value "[N/A]")
      (footprint "0603R")
      (description "Resistor")
      (fields (field (name "PUBLISHER") "Altium Limited"))
      (libsource (lib "Miscellaneous Devices") (part "Res1"))
    )
    (comp (ref "R283")
      (value "[N/A]")
      (footprint "0603R")
      (description "Resistor")
      (fields (field (name "PUBLISHER") "Altium Limited"))
      (libsource (lib "Miscellaneous Devices") (part "Res1"))
    )
    (comp (ref "R284")
      (value "0")
      (footprint "0603R")
      (description "Resistor")
      (fields (field (name "PUBLISHER") "Altium Limited"))
      (libsource (lib "Miscellaneous Devices") (part "Res1"))
    )
    (comp (ref "R285")
      (value "33")
      (footprint "0402R")
      (description "Resistor")
      (fields (field (name "PUBLISHER") "Altium Limited"))
      (libsource (lib "Miscellaneous Devices") (part "Res1"))
    )
    (comp (ref "R286")
      (value "33")
      (footprint "0402R")
      (description "Resistor")
      (fields (field (name "PUBLISHER") "Altium Limited"))
      (libsource (lib "Miscellaneous Devices") (part "Res1"))
    )
    (comp (ref "R287")
      (value "33")
      (footprint "0402R")
      (description "Resistor")
      (fields (field (name "PUBLISHER") "Altium Limited"))
      (libsource (lib "Miscellaneous Devices") (part "Res1"))
    )
    (comp (ref "R288")
      (value "33")
      (footprint "0402R")
      (description "Resistor")
      (fields (field (name "PUBLISHER") "Altium Limited"))
      (libsource (lib "Miscellaneous Devices") (part "Res1"))
    )
    (comp (ref "R289")
      (value "33")
      (footprint "0402R")
      (description "Resistor")
      (fields (field (name "PUBLISHER") "Altium Limited"))
      (libsource (lib "Miscellaneous Devices") (part "Res1"))
    )
    (comp (ref "R290")
      (value "33")
      (footprint "0402R")
      (description "Resistor")
      (fields (field (name "PUBLISHER") "Altium Limited"))
      (libsource (lib "Miscellaneous Devices") (part "Res1"))
    )
    (comp (ref "R291")
      (value "33")
      (footprint "0402R")
      (description "Resistor")
      (fields (field (name "PUBLISHER") "Altium Limited"))
      (libsource (lib "Miscellaneous Devices") (part "Res1"))
    )
    (comp (ref "R292")
      (value "[N/A]")
      (footprint "0603R")
      (description "Resistor")
      (fields (field (name "PUBLISHER") "Altium Limited"))
      (libsource (lib "Miscellaneous Devices") (part "Res1"))
    )
    (comp (ref "R293")
      (value "0")
      (footprint "0603R")
      (description "Resistor")
      (fields (field (name "PUBLISHER") "Altium Limited"))
      (libsource (lib "Miscellaneous Devices") (part "Res1"))
    )
    (comp (ref "R294")
      (value "0")
      (footprint "0603R")
      (description "Resistor")
      (fields (field (name "PUBLISHER") "Altium Limited"))
      (libsource (lib "Miscellaneous Devices") (part "Res1"))
    )
    (comp (ref "R295")
      (value "0")
      (footprint "0603R")
      (description "Resistor")
      (fields (field (name "PUBLISHER") "Altium Limited"))
      (libsource (lib "Miscellaneous Devices") (part "Res1"))
    )
    (comp (ref "SB7")
      (value "~")
      (footprint "JP2_SMD")
      (description "Circuit Breaker")
      (fields (field (name "PUBLISHER") "Altium Limited"))
      (libsource (lib "Miscellaneous Devices") (part "Circuit Breaker"))
    )
    (comp (ref "SB8")
      (value "~")
      (footprint "JP2_SMD")
      (description "Circuit Breaker")
      (fields (field (name "PUBLISHER") "Altium Limited"))
      (libsource (lib "Miscellaneous Devices") (part "Circuit Breaker"))
    )
    (comp (ref "SW1")
      (value "09.03290.01")
      (footprint "SW1_3TH_2R54_10X2R5")
      (description "SPDT Subminiature Toggle Switch, Right Angle Mounting, Vertical Actuation")
      (fields (field (name "PUBLISHER") "Altium Limited"))
      (libsource (lib "mb1045") (part "SW-SPDT"))
    )
    (comp (ref "SW2")
      (value "09.03290.01")
      (footprint "SW1_3TH_2R54_10X2R5")
      (description "SPDT Subminiature Toggle Switch, Right Angle Mounting, Vertical Actuation")
      (fields (field (name "PUBLISHER") "Altium Limited"))
      (libsource (lib "mb1045") (part "SW-SPDT"))
    )
    (comp (ref "TP2") (value "VREF") (footprint "TP") (libsource (lib "*") (part "TP")))
    (comp (ref "TP5") (value "VDDA") (footprint "TP") (libsource (lib "*") (part "TP")))
    (comp (ref "U3")
      (value "STM32F4")
      (footprint "BGA216_0R8_13X13_SKT")
      (libsource (lib "mb1045") (part "Big_Manta_TFBGA216"))
    )
    (comp (ref "X1")
      (value "CM200C32.768KDZF")
      (footprint "XTAL_4SM_8X3R8")
      (libsource (lib "*") (part "MC306"))
    )
    (comp (ref "X2")
      (value "25MHz(with socket)")
      (footprint "XTAL_socket")
      (description "Crystal")
      (libsource (lib "*") (part "CRYSTAL"))
    )
  )
  (nets
    (net (code "1") (name "+3V3") (class "Default")
      (node (ref "JP8") (pin "1") (pintype "passive"))
      (node (ref "R22") (pin "2") (pinfunction "2_2") (pintype "passive"))
      (node (ref "SW1") (pin "1") (pintype "passive"))
      (node (ref "SW2") (pin "1") (pintype "passive"))
    )
    (net (code "2") (name "/A0") (class "Default")
      (node (ref "R231") (pin "2") (pinfunction "2_2") (pintype "passive"))
    )
    (net (code "3") (name "/A1") (class "Default")
      (node (ref "R226") (pin "2") (pinfunction "2_2") (pintype "passive"))
    )
    (net (code "4") (name "/A2") (class "Default")
      (node (ref "R224") (pin "2") (pinfunction "2_2") (pintype "passive"))
    )
    (net (code "5") (name "/A3") (class "Default")
      (node (ref "R221") (pin "2") (pinfunction "2_2") (pintype "passive"))
    )
    (net (code "6") (name "/A4") (class "Default")
      (node (ref "R217") (pin "2") (pinfunction "2_2") (pintype "passive"))
    )
    (net (code "7") (name "/A5") (class "Default")
      (node (ref "R213") (pin "2") (pinfunction "2_2") (pintype "passive"))
    )
    (net (code "8") (name "/A6") (class "Default")
      (node (ref "R253") (pin "2") (pinfunction "2_2") (pintype "passive"))
    )
    (net (code "9") (name "/A7") (class "Default")
      (node (ref "R250") (pin "2") (pinfunction "2_2") (pintype "passive"))
    )
    (net (code "10") (name "/A8") (class "Default")
      (node (ref "R254") (pin "2") (pinfunction "2_2") (pintype "passive"))
    )
    (net (code "11") (name "/A9") (class "Default")
      (node (ref "R273") (pin "2") (pinfunction "2_2") (pintype "passive"))
    )
    (net (code "12") (name "/A10") (class "Default")
      (node (ref "R258") (pin "2") (pinfunction "2_2") (pintype "passive"))
    )
    (net (code "13") (name "/A11") (class "Default")
      (node (ref "R257") (pin "2") (pinfunction "2_2") (pintype "passive"))
    )
    (net (code "14") (name "/A12") (class "Default")
      (node (ref "R285") (pin "2") (pinfunction "2_2") (pintype "passive"))
    )
    (net (code "15") (name "/A13") (class "Default")
      (node (ref "R269") (pin "2") (pinfunction "2_2") (pintype "passive"))
    )
    (net (code "16") (name "/A14") (class "Default")
      (node (ref "R286") (pin "2") (pinfunction "2_2") (pintype "passive"))
    )
    (net (code "17") (name "/A15") (class "Default")
      (node (ref "R271") (pin "2") (pinfunction "2_2") (pintype "passive"))
    )
    (net (code "18") (name "/A16") (class "Default")
      (node (ref "R272") (pin "1") (pinfunction "1_1") (pintype "passive"))
    )
    (net (code "19") (name "/A17") (class "Default")
      (node (ref "R287") (pin "2") (pinfunction "2_2") (pintype "passive"))
    )
    (net (code "20") (name "/A18") (class "Default")
      (node (ref "R270") (pin "2") (pinfunction "2_2") (pintype "passive"))
    )
    (net (code "21") (name "/A19") (class "Default")
      (node (ref "R36") (pin "2") (pinfunction "2_2") (pintype "passive"))
      (node (ref "R37") (pin "2") (pinfunction "2_2") (pintype "passive"))
    )
    (net (code "22") (name "/A20") (class "Default")
      (node (ref "R34") (pin "2") (pinfunction "2_2") (pintype "passive"))
      (node (ref "R35") (pin "2") (pinfunction "2_2") (pintype "passive"))
    )
    (net (code "23") (name "/A21") (class "Default")
      (node (ref "R24") (pin "2") (pinfunction "2_2") (pintype "passive"))
      (node (ref "R29") (pin "2") (pinfunction "2_2") (pintype "passive"))
    )
    (net (code "24") (name "/A22") (class "Default")
      (node (ref "R30") (pin "2") (pinfunction "2_2") (pintype "passive"))
      (node (ref "R32") (pin "2") (pinfunction "2_2") (pintype "passive"))
    )
    (net (code "25") (name "/A23") (class "Default")
      (node (ref "R40") (pin "2") (pinfunction "2_2") (pintype "passive"))
      (node (ref "R41") (pin "2") (pinfunction "2_2") (pintype "passive"))
    )
    (net (code "27") (name "/BOOT0") (class "Default")
      (node (ref "SW1") (pin "2") (pintype "passive"))
      (node (ref "U3") (pin "E6") (pinfunction "BOOT0_E6") (pintype "passive"))
    )
    (net (code "28") (name "/CAN1_RX") (class "Default")
      (node (ref "JP16") (pin "2") (pinfunction "NO_2") (pintype "passive"))
    )
    (net (code "29") (name "/CAN1_TX") (class "Default")
      (node (ref "R256") (pin "2") (pinfunction "2_2") (pintype "passive"))
    )
    (net (code "30") (name "/D0") (class "Default")
      (node (ref "R74") (pin "2") (pinfunction "2_2") (pintype "passive"))
    )
    (net (code "31") (name "/D1") (class "Default")
      (node (ref "R61") (pin "2") (pinfunction "2_2") (pintype "passive"))
    )
    (net (code "32") (name "/D2") (class "Default")
      (node (ref "R274") (pin "2") (pinfunction "2_2") (pintype "passive"))
    )
    (net (code "33") (name "/D3") (class "Default")
      (node (ref "R288") (pin "2") (pinfunction "2_2") (pintype "passive"))
    )
    (net (code "34") (name "/D4") (class "Default")
      (node (ref "R65") (pin "2") (pinfunction "2_2") (pintype "passive"))
    )
    (net (code "35") (name "/D5") (class "Default")
      (node (ref "R54") (pin "2") (pinfunction "2_2") (pintype "passive"))
    )
    (net (code "36") (name "/D6") (class "Default")
      (node (ref "R53") (pin "2") (pinfunction "2_2") (pintype "passive"))
    )
    (net (code "37") (name "/D7") (class "Default")
      (node (ref "R66") (pin "2") (pinfunction "2_2") (pintype "passive"))
    )
    (net (code "38") (name "/D8") (class "Default")
      (node (ref "R55") (pin "2") (pinfunction "2_2") (pintype "passive"))
    )
    (net (code "39") (name "/D9") (class "Default")
      (node (ref "R67") (pin "2") (pinfunction "2_2") (pintype "passive"))
    )
    (net (code "40") (name "/D10") (class "Default")
      (node (ref "R69") (pin "2") (pinfunction "2_2") (pintype "passive"))
    )
    (net (code "41") (name "/D11") (class "Default")
      (node (ref "R56") (pin "2") (pinfunction "2_2") (pintype "passive"))
    )
    (net (code "42") (name "/D12") (class "Default")
      (node (ref "R68") (pin "2") (pinfunction "2_2") (pintype "passive"))
    )
    (net (code "43") (name "/D13") (class "Default")
      (node (ref "R60") (pin "2") (pinfunction "2_2") (pintype "passive"))
    )
    (net (code "44") (name "/D14") (class "Default")
      (node (ref "R72") (pin "2") (pinfunction "2_2") (pintype "passive"))
    )
    (net (code "45") (name "/D15") (class "Default")
      (node (ref "R73") (pin "2") (pinfunction "2_2") (pintype "passive"))
    )
    (net (code "46") (name "/D16") (class "Default")
      (node (ref "R57") (pin "1") (pinfunction "1_1") (pintype "passive"))
    )
    (net (code "47") (name "/D17") (class "Default")
      (node (ref "R58") (pin "1") (pinfunction "1_1") (pintype "passive"))
    )
    (net (code "48") (name "/D18") (class "Default")
      (node (ref "R70") (pin "1") (pinfunction "1_1") (pintype "passive"))
    )
    (net (code "49") (name "/D19") (class "Default")
      (node (ref "R71") (pin "1") (pinfunction "1_1") (pintype "passive"))
    )
    (net (code "50") (name "/D20") (class "Default")
      (node (ref "R59") (pin "1") (pinfunction "1_1") (pintype "passive"))
    )
    (net (code "51") (name "/D21") (class "Default")
      (node (ref "R278") (pin "1") (pinfunction "1_1") (pintype "passive"))
    )
    (net (code "52") (name "/D22") (class "Default")
      (node (ref "R291") (pin "1") (pinfunction "1_1") (pintype "passive"))
    )
    (net (code "53") (name "/D23") (class "Default")
      (node (ref "R290") (pin "1") (pinfunction "1_1") (pintype "passive"))
    )
    (net (code "54") (name "/D24") (class "Default")
      (node (ref "R277") (pin "1") (pinfunction "1_1") (pintype "passive"))
    )
    (net (code "55") (name "/D25") (class "Default")
      (node (ref "R276") (pin "1") (pinfunction "1_1") (pintype "passive"))
    )
    (net (code "56") (name "/D26") (class "Default")
      (node (ref "R275") (pin "1") (pinfunction "1_1") (pintype "passive"))
    )
    (net (code "57") (name "/D27") (class "Default")
      (node (ref "R289") (pin "1") (pinfunction "1_1") (pintype "passive"))
    )
    (net (code "58") (name "/D28") (class "Default")
      (node (ref "R247") (pin "1") (pinfunction "1_1") (pintype "passive"))
    )
    (net (code "59") (name "/D29") (class "Default")
      (node (ref "R237") (pin "1") (pinfunction "1_1") (pintype "passive"))
    )
    (net (code "60") (name "/D30") (class "Default")
      (node (ref "R241") (pin "1") (pinfunction "1_1") (pintype "passive"))
    )
    (net (code "61") (name "/D31") (class "Default")
      (node (ref "R244") (pin "1") (pinfunction "1_1") (pintype "passive"))
    )
    (net (code "63") (name "/FMC_NWAIT") (class "Default") (node (ref "JP5") (pin "1") (pintype "passive")))
    (net (code "64") (name "/I2S3_SD") (class "Default") (node (ref "JP5") (pin "3") (pintype "passive")))
    (net (code "65") (name "/LCD_BL_CTRL") (class "Default")
      (node (ref "R283") (pin "2") (pinfunction "2_2") (pintype "passive"))
    )
    (net (code "67") (name "/LCD_G0") (class "Default")
      (node (ref "U3") (pin "J12") (pinfunction "PJ7_J12") (pintype "passive"))
    )
    (net (code "68") (name "/LCD_G1") (class "Default")
      (node (ref "U3") (pin "H12") (pinfunction "PJ8_H12") (pintype "passive"))
    )
    (net (code "69") (name "/LCD_G2") (class "Default")
      (node (ref "U3") (pin "J13") (pinfunction "PJ9_J13") (pintype "passive"))
    )
    (net (code "70") (name "/LCD_G3") (class "Default")
      (node (ref "U3") (pin "H13") (pinfunction "PJ10_H13") (pintype "passive"))
    )
    (net (code "71") (name "/LCD_G4") (class "Default")
      (node (ref "U3") (pin "G12") (pinfunction "PJ11_G12") (pintype "passive"))
    )
    (net (code "72") (name "/LCD_G5") (class "Default")
      (node (ref "U3") (pin "G13") (pinfunction "PK0_G13") (pintype "passive"))
    )
    (net (code "73") (name "/LCD_G6") (class "Default")
      (node (ref "U3") (pin "F12") (pinfunction "PK1_F12") (pintype "passive"))
    )
    (net (code "74") (name "/LCD_G7") (class "Default")
      (node (ref "U3") (pin "F13") (pinfunction "PK2_F13") (pintype "passive"))
    )
    (net (code "76") (name "/LCD_R0") (class "Default")
      (node (ref "U3") (pin "G4") (pinfunction "PI15_G4") (pintype "passive"))
    )
    (net (code "77") (name "/LCD_R1") (class "Default")
      (node (ref "U3") (pin "R6") (pinfunction "PJ0_R6") (pintype "passive"))
    )
    (net (code "78") (name "/LCD_R2") (class "Default")
      (node (ref "U3") (pin "R7") (pinfunction "PJ1_R7") (pintype "passive"))
    )
    (net (code "79") (name "/LCD_R3") (class "Default")
      (node (ref "U3") (pin "P7") (pinfunction "PJ2_P7") (pintype "passive"))
    )
    (net (code "80") (name "/LCD_R4") (class "Default")
      (node (ref "U3") (pin "N8") (pinfunction "PJ3_N8") (pintype "passive"))
    )
    (net (code "81") (name "/LCD_R5") (class "Default")
      (node (ref "U3") (pin "M9") (pinfunction "PJ4_M9") (pintype "passive"))
    )
    (net (code "82") (name "/LCD_R6") (class "Default")
      (node (ref "U3") (pin "M14") (pinfunction "PJ5_M14") (pintype "passive"))
    )
    (net (code "83") (name "/LCD_R7") (class "Default")
      (node (ref "U3") (pin "K12") (pinfunction "PJ6_K12") (pintype "passive"))
    )
    (net (code "85") (name "/MC_BusVoltage") (class "Default")
      (node (ref "R235") (pin "1") (pinfunction "1_1") (pintype "passive"))
    )
    (net (code "86") (name "/MC_CurrentA") (class "Default")
      (node (ref "R218") (pin "1") (pinfunction "1_1") (pintype "passive"))
    )
    (net (code "87") (name "/MC_CurrentB") (class "Default")
      (node (ref "R232") (pin "1") (pinfunction "1_1") (pintype "passive"))
    )
    (net (code "88") (name "/MC_CurrentC") (class "Default")
      (node (ref "R242") (pin "1") (pinfunction "1_1") (pintype "passive"))
    )
    (net (code "89") (name "/MC_DissipativeBrake") (class "Default")
      (node (ref "R240") (pin "1") (pinfunction "1_1") (pintype "passive"))
    )
    (net (code "90") (name "/MC_EnA") (class "Default")
      (node (ref "R223") (pin "2") (pinfunction "2_2") (pintype "passive"))
    )
    (net (code "91") (name "/MC_EnB") (class "Default")
      (node (ref "R210") (pin "2") (pinfunction "2_2") (pintype "passive"))
    )
    (net (code "92") (name "/MC_EnIndex") (class "Default")
      (node (ref "R215") (pin "2") (pinfunction "2_2") (pintype "passive"))
    )
    (net (code "93") (name "/MC_Heatsink") (class "Default")
      (node (ref "R263") (pin "1") (pinfunction "1_1") (pintype "passive"))
    )
    (net (code "94") (name "/MC_NTC") (class "Default")
      (node (ref "R246") (pin "2") (pinfunction "2_2") (pintype "passive"))
    )
    (net (code "95") (name "/MC_PFCpwm") (class "Default")
      (node (ref "R255") (pin "2") (pinfunction "2_2") (pintype "passive"))
    )
    (net (code "96") (name "/MC_PFCsync1") (class "Default")
      (node (ref "R268") (pin "2") (pinfunction "2_2") (pintype "passive"))
    )
    (net (code "97") (name "/MC_PFCsync2") (class "Default")
      (node (ref "R252") (pin "2") (pinfunction "2_2") (pintype "passive"))
    )
    (net (code "98") (name "/MC_UH") (class "Default")
      (node (ref "R292") (pin "1") (pinfunction "1_1") (pintype "passive"))
    )
    (net (code "99") (name "/MC_UL") (class "Default")
      (node (ref "R225") (pin "2") (pinfunction "2_2") (pintype "passive"))
    )
    (net (code "100") (name "/MC_VL") (class "Default")
      (node (ref "R282") (pin "1") (pinfunction "1_1") (pintype "passive"))
    )
    (net (code "101") (name "/MC_WH") (class "Default")
      (node (ref "R280") (pin "1") (pinfunction "1_1") (pintype "passive"))
    )
    (net (code "102") (name "/MC_WL") (class "Default")
      (node (ref "R234") (pin "1") (pinfunction "1_1") (pintype "passive"))
    )
    (net (code "103") (name "/MIC_CK") (class "Default")
      (node (ref "R45") (pin "2") (pinfunction "2_2") (pintype "passive"))
    )
    (net (code "104") (name "/MII_COL") (class "Default")
      (node (ref "SB8") (pin "2") (pinfunction "2_2") (pintype "passive"))
    )
    (net (code "105") (name "/MII_CRS") (class "Default")
      (node (ref "SB7") (pin "1") (pinfunction "1_1") (pintype "passive"))
    )
    (net (code "106") (name "/MII_MCO") (class "Default")
      (node (ref "R279") (pin "2") (pinfunction "2_2") (pintype "passive"))
    )
    (net (code "107") (name "/MII_MDC") (class "Default")
      (node (ref "R222") (pin "1") (pinfunction "1_1") (pintype "passive"))
    )
    (net (code "108") (name "/MII_MDIO") (class "Default")
      (node (ref "R211") (pin "2") (pinfunction "2_2") (pintype "passive"))
    )
    (net (code "109") (name "/MII_RXD0") (class "Default")
      (node (ref "R239") (pin "1") (pinfunction "1_1") (pintype "passive"))
    )
    (net (code "110") (name "/MII_RXD1") (class "Default")
      (node (ref "R267") (pin "1") (pinfunction "1_1") (pintype "passive"))
    )
    (net (code "111") (name "/MII_RX_CLK") (class "Default")
      (node (ref "R214") (pin "2") (pinfunction "2_2") (pintype "passive"))
    )
    (net (code "112") (name "/MII_RX_DV") (class "Default")
      (node (ref "R227") (pin "2") (pinfunction "2_2") (pintype "passive"))
    )
    (net (code "113") (name "/MII_RX_ER") (class "Default")
      (node (ref "R43") (pin "1") (pinfunction "1_1") (pintype "passive"))
    )
    (net (code "114") (name "/MII_TXD0") (class "Default")
      (node (ref "R233") (pin "2") (pinfunction "2_2") (pintype "passive"))
    )
    (net (code "115") (name "/MII_TXD1") (class "Default")
      (node (ref "R236") (pin "2") (pinfunction "2_2") (pintype "passive"))
    )
    (net (code "116") (name "/MII_TXD2") (class "Default")
      (node (ref "R228") (pin "1") (pinfunction "1_1") (pintype "passive"))
    )
    (net (code "117") (name "/MII_TXD3") (class "Default")
      (node (ref "R243") (pin "1") (pinfunction "1_1") (pintype "passive"))
    )
    (net (code "118") (name "/MII_TX_CLK") (class "Default")
      (node (ref "R238") (pin "1") (pinfunction "1_1") (pintype "passive"))
    )
    (net (code "119") (name "/MII_TX_EN") (class "Default")
      (node (ref "R249") (pin "2") (pinfunction "2_2") (pintype "passive"))
    )
    (net (code "120") (name "/PA0") (class "Default")
      (node (ref "R219") (pin "1") (pinfunction "1_1") (pintype "passive"))
      (node (ref "R223") (pin "1") (pinfunction "1_1") (pintype "passive"))
      (node (ref "SB7") (pin "2") (pinfunction "2_2") (pintype "passive"))
      (node (ref "U3") (pin "N3") (pinfunction "PA0-WKUP_N3") (pintype "passive"))
    )
    (net (code "121") (name "/PA1") (class "Default")
      (node (ref "R210") (pin "1") (pinfunction "1_1") (pintype "passive"))
      (node (ref "R214") (pin "1") (pinfunction "1_1") (pintype "passive"))
      (node (ref "U3") (pin "N2") (pinfunction "PA1_N2") (pintype "passive"))
    )
    (net (code "122") (name "/PA2") (class "Default")
      (node (ref "R211") (pin "1") (pinfunction "1_1") (pintype "passive"))
      (node (ref "R215") (pin "1") (pinfunction "1_1") (pintype "passive"))
      (node (ref "U3") (pin "P2") (pinfunction "PA2_P2") (pintype "passive"))
    )
    (net (code "123") (name "/PA3") (class "Default")
      (node (ref "U3") (pin "R2") (pinfunction "PA3_R2") (pintype "passive"))
    )
    (net (code "124") (name "/PA4") (class "Default")
      (node (ref "U3") (pin "N4") (pinfunction "PA4_N4") (pintype "passive"))
    )
    (net (code "125") (name "/PA5") (class "Default")
      (node (ref "U3") (pin "P4") (pinfunction "PA5_P4") (pintype "passive"))
    )
    (net (code "126") (name "/PA6") (class "Default")
      (node (ref "U3") (pin "P3") (pinfunction "PA6_P3") (pintype "passive"))
    )
    (net (code "127") (name "/PA7") (class "Default")
      (node (ref "R225") (pin "1") (pinfunction "1_1") (pintype "passive"))
      (node (ref "R227") (pin "1") (pinfunction "1_1") (pintype "passive"))
      (node (ref "U3") (pin "R3") (pinfunction "PA7_R3") (pintype "passive"))
    )
    (net (code "128") (name "/PA8") (class "Default")
      (node (ref "R268") (pin "1") (pinfunction "1_1") (pintype "passive"))
      (node (ref "R279") (pin "1") (pinfunction "1_1") (pintype "passive"))
      (node (ref "R283") (pin "1") (pinfunction "1_1") (pintype "passive"))
      (node (ref "U3") (pin "F15") (pinfunction "PA8_F15") (pintype "passive"))
    )
    (net (code "129") (name "/PA9") (class "Default")
      (node (ref "R262") (pin "1") (pinfunction "1_1") (pintype "passive"))
      (node (ref "R266") (pin "1") (pinfunction "1_1") (pintype "passive"))
      (node (ref "U3") (pin "E15") (pinfunction "PA9_E15") (pintype "passive"))
    )
    (net (code "130") (name "/PA10") (class "Default")
      (node (ref "U3") (pin "D15") (pinfunction "PA10_D15") (pintype "passive"))
    )
    (net (code "131") (name "/PA11") (class "Default")
      (node (ref "JP16") (pin "1") (pinfunction "COMMON_1") (pintype "passive"))
      (node (ref "R255") (pin "1") (pinfunction "1_1") (pintype "passive"))
      (node (ref "U3") (pin "C15") (pinfunction "PA11_C15") (pintype "passive"))
    )
    (net (code "132") (name "/PA12") (class "Default")
      (node (ref "R252") (pin "1") (pinfunction "1_1") (pintype "passive"))
      (node (ref "R256") (pin "1") (pinfunction "1_1") (pintype "passive"))
      (node (ref "R261") (pin "1") (pinfunction "1_1") (pintype "passive"))
      (node (ref "U3") (pin "B15") (pinfunction "PA12_B15") (pintype "passive"))
    )
    (net (code "133") (name "/PA13") (class "Default")
      (node (ref "U3") (pin "A15") (pinfunction "PA13_A15") (pintype "passive"))
    )
    (net (code "134") (name "/PA14") (class "Default")
      (node (ref "U3") (pin "A14") (pinfunction "PA14_A14") (pintype "passive"))
    )
    (net (code "135") (name "/PA15") (class "Default")
      (node (ref "U3") (pin "A13") (pinfunction "PA15_A13") (pintype "passive"))
    )
    (net (code "136") (name "/PAR_D7") (class "Default")
      (node (ref "R114") (pin "1") (pinfunction "1_1") (pintype "passive"))
    )
    (net (code "139") (name "/PB0") (class "Default")
      (node (ref "R282") (pin "2") (pinfunction "2_2") (pintype "passive"))
      (node (ref "U3") (pin "R5") (pinfunction "PB0_R5") (pintype "passive"))
    )
    (net (code "140") (name "/PB1") (class "Default")
      (node (ref "R234") (pin "2") (pinfunction "2_2") (pintype "passive"))
      (node (ref "U3") (pin "R4") (pinfunction "PB1_R4") (pintype "passive"))
    )
    (net (code "141") (name "/PB2") (class "Default")
      (node (ref "R5") (pin "2") (pinfunction "2_2") (pintype "passive"))
      (node (ref "U3") (pin "M5") (pinfunction "PB2_M5") (pintype "passive"))
    )
    (net (code "142") (name "/PB3") (class "Default")
      (node (ref "JP4") (pin "2") (pintype "passive"))
      (node (ref "U3") (pin "A10") (pinfunction "PB3_A10") (pintype "passive"))
    )
    (net (code "143") (name "/PB4") (class "Default")
      (node (ref "U3") (pin "A9") (pinfunction "PB4_A9") (pintype "passive"))
    )
    (net (code "144") (name "/PB5") (class "Default")
      (node (ref "U3") (pin "A8") (pinfunction "PB5_A8") (pintype "passive"))
    )
    (net (code "145") (name "/PB6") (class "Default")
      (node (ref "U3") (pin "B6") (pinfunction "PB6_B6") (pintype "passive"))
    )
    (net (code "146") (name "/PB7") (class "Default")
      (node (ref "U3") (pin "B5") (pinfunction "PB7_B5") (pintype "passive"))
    )
    (net (code "147") (name "/PB8") (class "Default")
      (node (ref "R240") (pin "2") (pinfunction "2_2") (pintype "passive"))
      (node (ref "R243") (pin "2") (pinfunction "2_2") (pintype "passive"))
      (node (ref "U3") (pin "A7") (pinfunction "PB8_A7") (pintype "passive"))
    )
    (net (code "148") (name "/PB9") (class "Default")
      (node (ref "U3") (pin "B4") (pinfunction "PB9_B4") (pintype "passive"))
    )
    (net (code "149") (name "/PB10") (class "Default")
      (node (ref "U3") (pin "P12") (pinfunction "PB10_P12") (pintype "passive"))
    )
    (net (code "150") (name "/PB11") (class "Default")
      (node (ref "U3") (pin "R13") (pinfunction "PB11_R13") (pintype "passive"))
    )
    (net (code "151") (name "/PB12") (class "Default")
      (node (ref "R260") (pin "2") (pinfunction "2_2") (pintype "passive"))
      (node (ref "U3") (pin "L13") (pinfunction "PB12_L13") (pintype "passive"))
    )
    (net (code "152") (name "/PB13") (class "Default")
      (node (ref "R264") (pin "2") (pinfunction "2_2") (pintype "passive"))
      (node (ref "U3") (pin "K14") (pinfunction "PB13_K14") (pintype "passive"))
    )
    (net (code "153") (name "/PB14") (class "Default")
      (node (ref "U3") (pin "R14") (pinfunction "PB14_R14") (pintype "passive"))
    )
    (net (code "154") (name "/PB15") (class "Default")
      (node (ref "U3") (pin "R15") (pinfunction "PB15_R15") (pintype "passive"))
    )
    (net (code "156") (name "/PC0") (class "Default")
      (node (ref "U3") (pin "M2") (pinfunction "PC0_M2") (pintype "passive"))
    )
    (net (code "157") (name "/PC1") (class "Default")
      (node (ref "R218") (pin "2") (pinfunction "2_2") (pintype "passive"))
      (node (ref "R222") (pin "2") (pinfunction "2_2") (pintype "passive"))
      (node (ref "U3") (pin "M3") (pinfunction "PC1_M3") (pintype "passive"))
    )
    (net (code "158") (name "/PC2") (class "Default")
      (node (ref "R228") (pin "2") (pinfunction "2_2") (pintype "passive"))
      (node (ref "R232") (pin "2") (pinfunction "2_2") (pintype "passive"))
      (node (ref "U3") (pin "M4") (pinfunction "PC2_M4") (pintype "passive"))
    )
    (net (code "159") (name "/PC3") (class "Default")
      (node (ref "R238") (pin "2") (pinfunction "2_2") (pintype "passive"))
      (node (ref "R242") (pin "2") (pinfunction "2_2") (pintype "passive"))
      (node (ref "U3") (pin "L4") (pinfunction "PC3_L4") (pintype "passive"))
    )
    (net (code "160") (name "/PC4") (class "Default")
      (node (ref "R235") (pin "2") (pinfunction "2_2") (pintype "passive"))
      (node (ref "R239") (pin "2") (pinfunction "2_2") (pintype "passive"))
      (node (ref "U3") (pin "N5") (pinfunction "PC4_N5") (pintype "passive"))
    )
    (net (code "161") (name "/PC5") (class "Default")
      (node (ref "R263") (pin "2") (pinfunction "2_2") (pintype "passive"))
      (node (ref "R267") (pin "2") (pinfunction "2_2") (pintype "passive"))
      (node (ref "U3") (pin "P5") (pinfunction "PC5_P5") (pintype "passive"))
    )
    (net (code "162") (name "/PC6") (class "Default")
      (node (ref "JP4") (pin "3") (pintype "passive"))
      (node (ref "R292") (pin "2") (pinfunction "2_2") (pintype "passive"))
      (node (ref "U3") (pin "H15") (pinfunction "PC6_H15") (pintype "passive"))
    )
    (net (code "163") (name "/PC7") (class "Default")
      (node (ref "R45") (pin "1") (pinfunction "1_1") (pintype "passive"))
      (node (ref "U3") (pin "G15") (pinfunction "PC7_G15") (pintype "passive"))
    )
    (net (code "164") (name "/PC8") (class "Default")
      (node (ref "R280") (pin "2") (pinfunction "2_2") (pintype "passive"))
      (node (ref "R281") (pin "2") (pinfunction "2_2") (pintype "passive"))
      (node (ref "U3") (pin "G14") (pinfunction "PC8_G14") (pintype "passive"))
    )
    (net (code "165") (name "/PC9") (class "Default")
      (node (ref "R265") (pin "2") (pinfunction "2_2") (pintype "passive"))
      (node (ref "U3") (pin "F14") (pinfunction "PC9_F14") (pintype "passive"))
    )
    (net (code "166") (name "/PC10") (class "Default")
      (node (ref "R293") (pin "2") (pinfunction "2_2") (pintype "passive"))
      (node (ref "U3") (pin "B14") (pinfunction "PC10_B14") (pintype "passive"))
    )
    (net (code "167") (name "/PC11") (class "Default")
      (node (ref "R284") (pin "2") (pinfunction "2_2") (pintype "passive"))
      (node (ref "U3") (pin "B13") (pinfunction "PC11_B13") (pintype "passive"))
    )
    (net (code "168") (name "/PC12") (class "Default")
      (node (ref "U3") (pin "A12") (pinfunction "PC12_A12") (pintype "passive"))
    )
    (net (code "169") (name "/PC13") (class "Default")
      (node (ref "U3") (pin "D1") (pinfunction "PC13-ANTI_TAMP_D1") (pintype "passive"))
    )
    (net (code "170") (name "/PC14") (class "Default")
      (node (ref "R19") (pin "2") (pinfunction "2_2") (pintype "passive"))
      (node (ref "U3") (pin "E1") (pinfunction "PC14-OSC32_IN_E1") (pintype "passive"))
    )
    (net (code "171") (name "/PC15") (class "Default")
      (node (ref "R18") (pin "2") (pinfunction "2_2") (pintype "passive"))
      (node (ref "U3") (pin "F1") (pinfunction "PC15-OSC32_OUT_F1") (pintype "passive"))
    )
    (net (code "173") (name "/PD2") (class "Default")
      (node (ref "R294") (pin "2") (pinfunction "2_2") (pintype "passive"))
      (node (ref "U3") (pin "D12") (pinfunction "PD2_D12") (pintype "passive"))
    )
    (net (code "174") (name "/PD3") (class "Default")
      (node (ref "U3") (pin "C11") (pinfunction "PD3_C11") (pintype "passive"))
    )
    (net (code "175") (name "/PD4") (class "Default")
      (node (ref "U3") (pin "D11") (pinfunction "PD4_D11") (pintype "passive"))
    )
    (net (code "176") (name "/PD5") (class "Default")
      (node (ref "U3") (pin "C10") (pinfunction "PD5_C10") (pintype "passive"))
    )
    (net (code "177") (name "/PD6") (class "Default")
      (node (ref "JP5") (pin "2") (pintype "passive"))
      (node (ref "U3") (pin "B11") (pinfunction "PD6_B11") (pintype "passive"))
    )
    (net (code "178") (name "/PD7") (class "Default")
      (node (ref "U3") (pin "A11") (pinfunction "PD7_A11") (pintype "passive"))
    )
    (net (code "180") (name "/PE0") (class "Default")
      (node (ref "U3") (pin "A6") (pinfunction "PE0_A6") (pintype "passive"))
    )
    (net (code "181") (name "/PE1") (class "Default")
      (node (ref "U3") (pin "A5") (pinfunction "PE1_A5") (pintype "passive"))
    )
    (net (code "183") (name "/PF6") (class "Default")
      (node (ref "U3") (pin "K2") (pinfunction "PF6_K2") (pintype "passive"))
    )
    (net (code "184") (name "/PF7") (class "Default")
      (node (ref "U3") (pin "K1") (pinfunction "PF7_K1") (pintype "passive"))
    )
    (net (code "185") (name "/PF8") (class "Default")
      (node (ref "U3") (pin "L3") (pinfunction "PF8_L3") (pintype "passive"))
    )
    (net (code "186") (name "/PF9") (class "Default")
      (node (ref "U3") (pin "L2") (pinfunction "PF9_L2") (pintype "passive"))
    )
    (net (code "187") (name "/PF10") (class "Default")
      (node (ref "U3") (pin "L1") (pinfunction "PF10_L1") (pintype "passive"))
    )
    (net (code "188") (name "/PF11") (class "Default")
      (node (ref "R52") (pin "2") (pinfunction "2_2") (pintype "passive"))
    )
    (net (code "190") (name "/PG6") (class "Default")
      (node (ref "U3") (pin "J15") (pinfunction "PG6_J15") (pintype "passive"))
    )
    (net (code "191") (name "/PG7") (class "Default")
      (node (ref "U3") (pin "J14") (pinfunction "PG7_J14") (pintype "passive"))
    )
    (net (code "192") (name "/PG8") (class "Default")
      (node (ref "R62") (pin "2") (pinfunction "2_2") (pintype "passive"))
    )
    (net (code "193") (name "/PG9") (class "Default")
      (node (ref "U3") (pin "D9") (pinfunction "PG9_D9") (pintype "passive"))
    )
    (net (code "194") (name "/PG10") (class "Default")
      (node (ref "U3") (pin "C8") (pinfunction "PG10_C8") (pintype "passive"))
    )
    (net (code "195") (name "/PG11") (class "Default")
      (node (ref "R246") (pin "1") (pinfunction "1_1") (pintype "passive"))
      (node (ref "R249") (pin "1") (pinfunction "1_1") (pintype "passive"))
      (node (ref "U3") (pin "B8") (pinfunction "PG11_B8") (pintype "passive"))
    )
    (net (code "196") (name "/PG12") (class "Default")
      (node (ref "U3") (pin "C7") (pinfunction "PG12_C7") (pintype "passive"))
    )
    (net (code "197") (name "/PG13") (class "Default")
      (node (ref "R233") (pin "1") (pinfunction "1_1") (pintype "passive"))
      (node (ref "U3") (pin "B3") (pinfunction "PG13_B3") (pintype "passive"))
    )
    (net (code "198") (name "/PG14") (class "Default")
      (node (ref "R236") (pin "1") (pinfunction "1_1") (pintype "passive"))
      (node (ref "U3") (pin "A4") (pinfunction "PG14_A4") (pintype "passive"))
    )
    (net (code "199") (name "/PG15") (class "Default")
      (node (ref "R42") (pin "2") (pinfunction "2_2") (pintype "passive"))
    )
    (net (code "201") (name "/PH0") (class "Default")
      (node (ref "R20") (pin "1") (pinfunction "1_1") (pintype "passive"))
      (node (ref "U3") (pin "G1") (pinfunction "PH0-OSC_IN_G1") (pintype "passive"))
    )
    (net (code "202") (name "/PH1") (class "Default")
      (node (ref "C23") (pin "1") (pinfunction "1_1") (pintype "passive"))
      (node (ref "U3") (pin "H1") (pinfunction "PH1-OSC_OUT_H1") (pintype "passive"))
      (node (ref "X2") (pin "1") (pinfunction "1_1") (pintype "passive"))
    )
    (net (code "203") (name "/PH2") (class "Default")
      (node (ref "U3") (pin "K4") (pinfunction "PH2_K4") (pintype "passive"))
    )
    (net (code "204") (name "/PH3") (class "Default")
      (node (ref "R248") (pin "1") (pinfunction "1_1") (pintype "passive"))
    )
    (net (code "205") (name "/PH4") (class "Default")
      (node (ref "U3") (pin "H4") (pinfunction "PH4_H4") (pintype "passive"))
    )
    (net (code "206") (name "/PH5") (class "Default")
      (node (ref "R251") (pin "1") (pinfunction "1_1") (pintype "passive"))
    )
    (net (code "207") (name "/PH6") (class "Default")
      (node (ref "U3") (pin "P13") (pinfunction "PH6_P13") (pintype "passive"))
    )
    (net (code "208") (name "/PH7") (class "Default")
      (node (ref "U3") (pin "N13") (pinfunction "PH7_N13") (pintype "passive"))
    )
    (net (code "210") (name "/PI4") (class "Default")
      (node (ref "U3") (pin "C3") (pinfunction "PI4_C3") (pintype "passive"))
    )
    (net (code "211") (name "/PI5") (class "Default")
      (node (ref "U3") (pin "D3") (pinfunction "PI5_D3") (pintype "passive"))
    )
    (net (code "212") (name "/PI8") (class "Default")
      (node (ref "U3") (pin "C2") (pinfunction "PI8-ANTI_TAMP2_C2") (pintype "passive"))
    )
    (net (code "213") (name "/PI11") (class "Default")
      (node (ref "U3") (pin "F3") (pinfunction "PI11_F3") (pintype "passive"))
    )
    (net (code "214") (name "/PI12") (class "Default")
      (node (ref "U3") (pin "E3") (pinfunction "PI12_E3") (pintype "passive"))
    )
    (net (code "215") (name "/PI13") (class "Default")
      (node (ref "U3") (pin "G3") (pinfunction "PI13_G3") (pintype "passive"))
    )
    (net (code "216") (name "/PI14") (class "Default")
      (node (ref "R295") (pin "1") (pinfunction "1_1") (pintype "passive"))
    )
    (net (code "218") (name "/PJ12") (class "Default")
      (node (ref "U3") (pin "B10") (pinfunction "PJ12_B10") (pintype "passive"))
    )
    (net (code "219") (name "/PJ13") (class "Default")
      (node (ref "U3") (pin "B9") (pinfunction "PJ13_B9") (pintype "passive"))
    )
    (net (code "220") (name "/PJ14") (class "Default")
      (node (ref "U3") (pin "C9") (pinfunction "PJ14_C9") (pintype "passive"))
    )
    (net (code "221") (name "/PJ15") (class "Default")
      (node (ref "U3") (pin "D10") (pinfunction "PJ15_D10") (pintype "passive"))
    )
    (net (code "223") (name "/PK3") (class "Default")
      (node (ref "U3") (pin "D8") (pinfunction "PK3_D8") (pintype "passive"))
    )
    (net (code "224") (name "/PK4") (class "Default")
      (node (ref "U3") (pin "D7") (pinfunction "PK4_D7") (pintype "passive"))
    )
    (net (code "225") (name "/PK5") (class "Default")
      (node (ref "U3") (pin "C6") (pinfunction "PK5_C6") (pintype "passive"))
    )
    (net (code "226") (name "/PK6") (class "Default")
      (node (ref "U3") (pin "C5") (pinfunction "PK6_C5") (pintype "passive"))
    )
    (net (code "227") (name "/PK7") (class "Default")
      (node (ref "U3") (pin "C4") (pinfunction "PK7_C4") (pintype "passive"))
    )
    (net (code "229") (name "/RESET#") (class "Default")
      (node (ref "B1") (pin "2") (pinfunction "B0_2") (pintype "passive"))
      (node (ref "B1") (pin "3") (pinfunction "B1_3") (pintype "passive"))
      (node (ref "C91") (pin "2") (pinfunction "2_2") (pintype "passive"))
      (node (ref "U3") (pin "J1") (pinfunction "NRST_J1") (pintype "passive"))
    )
    (net (code "230") (name "/RS232{slash}IrDA_TX") (class "Default")
      (node (ref "R262") (pin "2") (pinfunction "2_2") (pintype "passive"))
    )
    (net (code "231") (name "/SAI1_SDA") (class "Default")
      (node (ref "R120") (pin "2") (pinfunction "2_2") (pintype "passive"))
    )
    (net (code "232") (name "/TDO{slash}SWO") (class "Default")
      (node (ref "JP4") (pin "1") (pintype "passive"))
    )
    (net (code "233") (name "/TRACE_CK") (class "Default")
      (node (ref "R38") (pin "1") (pinfunction "1_1") (pintype "passive"))
    )
    (net (code "234") (name "/TRACE_D0") (class "Default")
      (node (ref "R39") (pin "1") (pinfunction "1_1") (pintype "passive"))
    )
    (net (code "235") (name "/TRACE_D1") (class "Default")
      (node (ref "R33") (pin "1") (pinfunction "1_1") (pintype "passive"))
    )
    (net (code "236") (name "/TRACE_D2") (class "Default")
      (node (ref "R23") (pin "1") (pinfunction "1_1") (pintype "passive"))
    )
    (net (code "237") (name "/TRACE_D3") (class "Default")
      (node (ref "R128") (pin "1") (pinfunction "1_1") (pintype "passive"))
    )
    (net (code "239") (name "/USB_FS1_DP") (class "Default")
      (node (ref "R261") (pin "2") (pinfunction "2_2") (pintype "passive"))
    )
    (net (code "240") (name "/USB_FS2_ID") (class "Default")
      (node (ref "R260") (pin "1") (pinfunction "1_1") (pintype "passive"))
    )
    (net (code "241") (name "/WAKEUP") (class "Default")
      (node (ref "R219") (pin "2") (pinfunction "2_2") (pintype "passive"))
    )
    (net (code "242") (name "/uSD_CMD") (class "Default")
      (node (ref "R294") (pin "1") (pinfunction "1_1") (pintype "passive"))
    )
    (net (code "243") (name "/uSD_D0") (class "Default")
      (node (ref "R281") (pin "1") (pinfunction "1_1") (pintype "passive"))
    )
    (net (code "244") (name "/uSD_D1") (class "Default")
      (node (ref "R265") (pin "1") (pinfunction "1_1") (pintype "passive"))
    )
    (net (code "245") (name "/uSD_D2") (class "Default")
      (node (ref "R293") (pin "1") (pinfunction "1_1") (pintype "passive"))
    )
    (net (code "246") (name "/uSD_D3") (class "Default")
      (node (ref "R284") (pin "1") (pinfunction "1_1") (pintype "passive"))
    )
    (net (code "247") (name "GND") (class "Default")
      (node (ref "B1") (pin "1") (pinfunction "A0_1") (pintype "passive"))
      (node (ref "B1") (pin "4") (pinfunction "A1_4") (pintype "passive"))
      (node (ref "BT1") (pin "2") (pinfunction "-_2") (pintype "passive"))
      (node (ref "C103") (pin "2") (pinfunction "2_2") (pintype "passive"))
      (node (ref "C104") (pin "2") (pinfunction "2_2") (pintype "passive"))
      (node (ref "C105") (pin "2") (pinfunction "2_2") (pintype "passive"))
      (node (ref "C106") (pin "2") (pinfunction "2_2") (pintype "passive"))
      (node (ref "C107") (pin "1") (pinfunction "1_1") (pintype "passive"))
      (node (ref "C108") (pin "2") (pinfunction "2_2") (pintype "passive"))
      (node (ref "C109") (pin "2") (pinfunction "2_2") (pintype "passive"))
      (node (ref "C110") (pin "1") (pinfunction "1_1") (pintype "passive"))
      (node (ref "C111") (pin "2") (pinfunction "2_2") (pintype "passive"))
      (node (ref "C112") (pin "2") (pinfunction "2_2") (pintype "passive"))
      (node (ref "C113") (pin "2") (pinfunction "2_2") (pintype "passive"))
      (node (ref "C114") (pin "2") (pinfunction "2_2") (pintype "passive"))
      (node (ref "C115") (pin "2") (pinfunction "2_2") (pintype "passive"))
      (node (ref "C118") (pin "2") (pinfunction "2_2") (pintype "passive"))
      (node (ref "C119") (pin "2") (pinfunction "2_2") (pintype "passive"))
      (node (ref "C120") (pin "2") (pinfunction "2_2") (pintype "passive"))
      (node (ref "C121") (pin "2") (pinfunction "2_2") (pintype "passive"))
      (node (ref "C122") (pin "2") (pinfunction "2_2") (pintype "passive"))
      (node (ref "C123") (pin "2") (pinfunction "2_2") (pintype "passive"))
      (node (ref "C125") (pin "2") (pinfunction "2_2") (pintype "passive"))
      (node (ref "C126") (pin "2") (pinfunction "2_2") (pintype "passive"))
      (node (ref "C127") (pin "2") (pinfunction "2_2") (pintype "passive"))
      (node (ref "C128") (pin "2") (pinfunction "2_2") (pintype "passive"))
      (node (ref "C129") (pin "2") (pinfunction "2_2") (pintype "passive"))
      (node (ref "C130") (pin "2") (pinfunction "2_2") (pintype "passive"))
      (node (ref "C133") (pin "2") (pinfunction "2_2") (pintype "passive"))
      (node (ref "C20") (pin "2") (pinfunction "2_2") (pintype "passive"))
      (node (ref "C21") (pin "2") (pinfunction "2_2") (pintype "passive"))
      (node (ref "C22") (pin "2") (pinfunction "2_2") (pintype "passive"))
      (node (ref "C23") (pin "2") (pinfunction "2_2") (pintype "passive"))
      (node (ref "C32") (pin "2") (pinfunction "2_2") (pintype "passive"))
      (node (ref "C91") (pin "1") (pinfunction "1_1") (pintype "passive"))
      (node (ref "R21") (pin "2") (pinfunction "2_2") (pintype "passive"))
      (node (ref "R24") (pin "1") (pinfunction "1_1") (pintype "passive"))
      (node (ref "R245") (pin "1") (pinfunction "1_1") (pintype "passive"))
      (node (ref "R30") (pin "1") (pinfunction "1_1") (pintype "passive"))
      (node (ref "R35") (pin "1") (pinfunction "1_1") (pintype "passive"))
      (node (ref "R37") (pin "1") (pinfunction "1_1") (pintype "passive"))
      (node (ref "R41") (pin "1") (pinfunction "1_1") (pintype "passive"))
      (node (ref "SW1") (pin "3") (pintype "passive"))
      (node (ref "SW2") (pin "3") (pintype "passive"))
      (node (ref "U3") (pin "F10") (pinfunction "VSS2_F10") (pintype "passive"))
      (node (ref "U3") (pin "F2") (pinfunction "VSS13-VSS18_F2") (pintype "passive"))
      (node (ref "U3") (pin "F6") (pinfunction "VSS3_F6") (pintype "passive"))
      (node (ref "U3") (pin "F7") (pinfunction "VSS11_F7") (pintype "passive"))
      (node (ref "U3") (pin "F8") (pinfunction "VSS10_F8") (pintype "passive"))
      (node (ref "U3") (pin "F9") (pinfunction "VSS15_F9") (pintype "passive"))
      (node (ref "U3") (pin "G10") (pinfunction "VSS9_G10") (pintype "passive"))
      (node (ref "U3") (pin "G6") (pinfunction "VSS17_G6") (pintype "passive"))
      (node (ref "U3") (pin "H10") (pinfunction "VSS20_H10") (pintype "passive"))
      (node (ref "U3") (pin "H6") (pinfunction "VSS5_H6") (pintype "passive"))
      (node (ref "U3") (pin "J10") (pinfunction "VSS8_J10") (pintype "passive"))
      (node (ref "U3") (pin "J6") (pinfunction "VSS12_J6") (pintype "passive"))
      (node (ref "U3") (pin "K10") (pinfunction "VSS14_K10") (pintype "passive"))
      (node (ref "U3") (pin "K6") (pinfunction "VSS4_K6") (pintype "passive"))
      (node (ref "U3") (pin "K7") (pinfunction "VSS6_K7") (pintype "passive"))
      (node (ref "U3") (pin "K8") (pinfunction "VSS7_K8") (pintype "passive"))
      (node (ref "U3") (pin "K9") (pinfunction "VSS1_K9") (pintype "passive"))
      (node (ref "U3") (pin "L6") (pinfunction "VSS19_L6") (pintype "passive"))
      (node (ref "U3") (pin "M1") (pinfunction "VSSA_M1") (pintype "passive"))
      (node (ref "U3") (pin "N1") (pinfunction "VREF-_N1") (pintype "passive"))
    )
    (net (code "248") (name "Net-(BT1-+)") (class "Default")
      (node (ref "BT1") (pin "1") (pinfunction "+_1") (pintype "passive"))
      (node (ref "JP8") (pin "3") (pintype "passive"))
    )
    (net (code "249") (name "Net-(C20-Pad1)") (class "Default")
      (node (ref "C20") (pin "1") (pinfunction "1_1") (pintype "passive"))
      (node (ref "R20") (pin "2") (pinfunction "2_2") (pintype "passive"))
      (node (ref "X2") (pin "2") (pinfunction "2_2") (pintype "passive"))
    )
    (net (code "250") (name "Net-(C21-Pad1)") (class "Default")
      (node (ref "C21") (pin "1") (pinfunction "1_1") (pintype "passive"))
      (node (ref "R18") (pin "1") (pinfunction "1_1") (pintype "passive"))
      (node (ref "X1") (pin "4") (pinfunction "4_4") (pintype "passive"))
    )
    (net (code "251") (name "Net-(C22-Pad1)") (class "Default")
      (node (ref "C22") (pin "1") (pinfunction "1_1") (pintype "passive"))
      (node (ref "R19") (pin "1") (pinfunction "1_1") (pintype "passive"))
      (node (ref "X1") (pin "1") (pinfunction "1_1") (pintype "passive"))
    )
    (net (code "252") (name "Net-(R5-Pad1)") (class "Default")
      (node (ref "R5") (pin "1") (pinfunction "1_1") (pintype "passive"))
      (node (ref "SW2") (pin "2") (pintype "passive"))
    )
    (net (code "253") (name "Net-(U3A-PDR_ON)") (class "Default")
      (node (ref "R21") (pin "1") (pinfunction "1_1") (pintype "passive"))
      (node (ref "R22") (pin "1") (pinfunction "1_1") (pintype "passive"))
      (node (ref "U3") (pin "E5") (pinfunction "PDR_ON_E5") (pintype "passive"))
    )
    (net (code "254") (name "Net-(U3B-PD0)") (class "Default")
      (node (ref "R274") (pin "1") (pinfunction "1_1") (pintype "passive"))
      (node (ref "U3") (pin "B12") (pinfunction "PD0_B12") (pintype "passive"))
    )
    (net (code "255") (name "Net-(U3B-PD1)") (class "Default")
      (node (ref "R288") (pin "1") (pinfunction "1_1") (pintype "passive"))
      (node (ref "U3") (pin "C12") (pinfunction "PD1_C12") (pintype "passive"))
    )
    (net (code "256") (name "Net-(U3B-PD8)") (class "Default")
      (node (ref "R60") (pin "1") (pinfunction "1_1") (pintype "passive"))
      (node (ref "U3") (pin "L15") (pinfunction "PD8_L15") (pintype "passive"))
    )
    (net (code "257") (name "Net-(U3B-PD9)") (class "Default")
      (node (ref "R72") (pin "1") (pinfunction "1_1") (pintype "passive"))
      (node (ref "U3") (pin "L14") (pinfunction "PD9_L14") (pintype "passive"))
    )
    (net (code "258") (name "Net-(U3B-PD10)") (class "Default")
      (node (ref "R73") (pin "1") (pinfunction "1_1") (pintype "passive"))
      (node (ref "U3") (pin "K15") (pinfunction "PD10_K15") (pintype "passive"))
    )
    (net (code "259") (name "Net-(U3B-PD11)") (class "Default")
      (node (ref "R272") (pin "2") (pinfunction "2_2") (pintype "passive"))
      (node (ref "U3") (pin "N10") (pinfunction "PD11_N10") (pintype "passive"))
    )
    (net (code "260") (name "Net-(U3B-PD12)") (class "Default")
      (node (ref "R287") (pin "1") (pinfunction "1_1") (pintype "passive"))
      (node (ref "U3") (pin "M10") (pinfunction "PD12_M10") (pintype "passive"))
    )
    (net (code "261") (name "Net-(U3B-PD13)") (class "Default")
      (node (ref "R270") (pin "1") (pinfunction "1_1") (pintype "passive"))
      (node (ref "U3") (pin "M11") (pinfunction "PD13_M11") (pintype "passive"))
    )
    (net (code "262") (name "Net-(U3B-PD14)") (class "Default")
      (node (ref "R74") (pin "1") (pinfunction "1_1") (pintype "passive"))
      (node (ref "U3") (pin "L12") (pinfunction "PD14_L12") (pintype "passive"))
    )
    (net (code "263") (name "Net-(U3B-PD15)") (class "Default")
      (node (ref "R61") (pin "1") (pinfunction "1_1") (pintype "passive"))
      (node (ref "U3") (pin "K13") (pinfunction "PD15_K13") (pintype "passive"))
    )
    (net (code "264") (name "Net-(U3B-PE2)") (class "Default")
      (node (ref "R38") (pin "2") (pinfunction "2_2") (pintype "passive"))
      (node (ref "R40") (pin "1") (pinfunction "1_1") (pintype "passive"))
      (node (ref "U3") (pin "A3") (pinfunction "PE2_A3") (pintype "passive"))
    )
    (net (code "265") (name "Net-(U3B-PE3)") (class "Default")
      (node (ref "R36") (pin "1") (pinfunction "1_1") (pintype "passive"))
      (node (ref "R39") (pin "2") (pinfunction "2_2") (pintype "passive"))
      (node (ref "U3") (pin "A2") (pinfunction "PE3_A2") (pintype "passive"))
    )
    (net (code "266") (name "Net-(U3B-PE4)") (class "Default")
      (node (ref "R33") (pin "2") (pinfunction "2_2") (pintype "passive"))
      (node (ref "R34") (pin "1") (pinfunction "1_1") (pintype "passive"))
      (node (ref "U3") (pin "A1") (pinfunction "PE4_A1") (pintype "passive"))
    )
    (net (code "267") (name "Net-(U3B-PE5)") (class "Default")
      (node (ref "R23") (pin "2") (pinfunction "2_2") (pintype "passive"))
      (node (ref "R29") (pin "1") (pinfunction "1_1") (pintype "passive"))
      (node (ref "U3") (pin "B1") (pinfunction "PE5_B1") (pintype "passive"))
    )
    (net (code "268") (name "Net-(U3B-PE6)") (class "Default")
      (node (ref "R114") (pin "2") (pinfunction "2_2") (pintype "passive"))
      (node (ref "R120") (pin "1") (pinfunction "1_1") (pintype "passive"))
      (node (ref "R128") (pin "2") (pinfunction "2_2") (pintype "passive"))
      (node (ref "R32") (pin "1") (pinfunction "1_1") (pintype "passive"))
      (node (ref "U3") (pin "B2") (pinfunction "PE6_B2") (pintype "passive"))
    )
    (net (code "269") (name "Net-(U3B-PE7)") (class "Default")
      (node (ref "R65") (pin "1") (pinfunction "1_1") (pintype "passive"))
      (node (ref "U3") (pin "R8") (pinfunction "PE7_R8") (pintype "passive"))
    )
    (net (code "270") (name "Net-(U3B-PE8)") (class "Default")
      (node (ref "R54") (pin "1") (pinfunction "1_1") (pintype "passive"))
      (node (ref "U3") (pin "N9") (pinfunction "PE8_N9") (pintype "passive"))
    )
    (net (code "271") (name "Net-(U3B-PE9)") (class "Default")
      (node (ref "R53") (pin "1") (pinfunction "1_1") (pintype "passive"))
      (node (ref "U3") (pin "P9") (pinfunction "PE9_P9") (pintype "passive"))
    )
    (net (code "272") (name "Net-(U3B-PE10)") (class "Default")
      (node (ref "R66") (pin "1") (pinfunction "1_1") (pintype "passive"))
      (node (ref "U3") (pin "R9") (pinfunction "PE10_R9") (pintype "passive"))
    )
    (net (code "273") (name "Net-(U3B-PE11)") (class "Default")
      (node (ref "R55") (pin "1") (pinfunction "1_1") (pintype "passive"))
      (node (ref "U3") (pin "P10") (pinfunction "PE11_P10") (pintype "passive"))
    )
    (net (code "274") (name "Net-(U3B-PE12)") (class "Default")
      (node (ref "R67") (pin "1") (pinfunction "1_1") (pintype "passive"))
      (node (ref "U3") (pin "R10") (pinfunction "PE12_R10") (pintype "passive"))
    )
    (net (code "275") (name "Net-(U3B-PE13)") (class "Default")
      (node (ref "R69") (pin "1") (pinfunction "1_1") (pintype "passive"))
      (node (ref "U3") (pin "R12") (pinfunction "PE13_R12") (pintype "passive"))
    )
    (net (code "276") (name "Net-(U3B-PE14)") (class "Default")
      (node (ref "R56") (pin "1") (pinfunction "1_1") (pintype "passive"))
      (node (ref "U3") (pin "P11") (pinfunction "PE14_P11") (pintype "passive"))
    )
    (net (code "277") (name "Net-(U3B-PE15)") (class "Default")
      (node (ref "R68") (pin "1") (pinfunction "1_1") (pintype "passive"))
      (node (ref "U3") (pin "R11") (pinfunction "PE15_R11") (pintype "passive"))
    )
    (net (code "278") (name "Net-(U3B-PF0)") (class "Default")
      (node (ref "R231") (pin "1") (pinfunction "1_1") (pintype "passive"))
      (node (ref "U3") (pin "D2") (pinfunction "PF0_D2") (pintype "passive"))
    )
    (net (code "279") (name "Net-(U3B-PF1)") (class "Default")
      (node (ref "R226") (pin "1") (pinfunction "1_1") (pintype "passive"))
      (node (ref "U3") (pin "E2") (pinfunction "PF1_E2") (pintype "passive"))
    )
    (net (code "280") (name "Net-(U3B-PF2)") (class "Default")
      (node (ref "R224") (pin "1") (pinfunction "1_1") (pintype "passive"))
      (node (ref "U3") (pin "G2") (pinfunction "PF2_G2") (pintype "passive"))
    )
    (net (code "281") (name "Net-(U3B-PF3)") (class "Default")
      (node (ref "R221") (pin "1") (pinfunction "1_1") (pintype "passive"))
      (node (ref "U3") (pin "H2") (pinfunction "PF3_H2") (pintype "passive"))
    )
    (net (code "282") (name "Net-(U3B-PF4)") (class "Default")
      (node (ref "R217") (pin "1") (pinfunction "1_1") (pintype "passive"))
      (node (ref "U3") (pin "J2") (pinfunction "PF4_J2") (pintype "passive"))
    )
    (net (code "283") (name "Net-(U3B-PF5)") (class "Default")
      (node (ref "R213") (pin "1") (pinfunction "1_1") (pintype "passive"))
      (node (ref "U3") (pin "K3") (pinfunction "PF5_K3") (pintype "passive"))
    )
    (net (code "284") (name "Net-(U3B-PF11)") (class "Default")
      (node (ref "R52") (pin "1") (pinfunction "1_1") (pintype "passive"))
      (node (ref "U3") (pin "P8") (pinfunction "PF11_P8") (pintype "passive"))
    )
    (net (code "285") (name "Net-(U3B-PF12)") (class "Default")
      (node (ref "R253") (pin "1") (pinfunction "1_1") (pintype "passive"))
      (node (ref "U3") (pin "M6") (pinfunction "PF12_M6") (pintype "passive"))
    )
    (net (code "286") (name "Net-(U3B-PF13)") (class "Default")
      (node (ref "R250") (pin "1") (pinfunction "1_1") (pintype "passive"))
      (node (ref "U3") (pin "N6") (pinfunction "PF13_N6") (pintype "passive"))
    )
    (net (code "287") (name "Net-(U3B-PF14)") (class "Default")
      (node (ref "R254") (pin "1") (pinfunction "1_1") (pintype "passive"))
      (node (ref "U3") (pin "P6") (pinfunction "PF14_P6") (pintype "passive"))
    )
    (net (code "288") (name "Net-(U3B-PF15)") (class "Default")
      (node (ref "R273") (pin "1") (pinfunction "1_1") (pintype "passive"))
      (node (ref "U3") (pin "M8") (pinfunction "PF15_M8") (pintype "passive"))
    )
    (net (code "289") (name "Net-(U3B-PG0)") (class "Default")
      (node (ref "R258") (pin "1") (pinfunction "1_1") (pintype "passive"))
      (node (ref "U3") (pin "N7") (pinfunction "PG0_N7") (pintype "passive"))
    )
    (net (code "290") (name "Net-(U3B-PG1)") (class "Default")
      (node (ref "R257") (pin "1") (pinfunction "1_1") (pintype "passive"))
      (node (ref "U3") (pin "M7") (pinfunction "PG1_M7") (pintype "passive"))
    )
    (net (code "291") (name "Net-(U3B-PG2)") (class "Default")
      (node (ref "R285") (pin "1") (pinfunction "1_1") (pintype "passive"))
      (node (ref "U3") (pin "M13") (pinfunction "PG2_M13") (pintype "passive"))
    )
    (net (code "292") (name "Net-(U3B-PG3)") (class "Default")
      (node (ref "R269") (pin "1") (pinfunction "1_1") (pintype "passive"))
      (node (ref "U3") (pin "M12") (pinfunction "PG3_M12") (pintype "passive"))
    )
    (net (code "293") (name "Net-(U3B-PG4)") (class "Default")
      (node (ref "R286") (pin "1") (pinfunction "1_1") (pintype "passive"))
      (node (ref "U3") (pin "N12") (pinfunction "PG4_N12") (pintype "passive"))
    )
    (net (code "294") (name "Net-(U3B-PG5)") (class "Default")
      (node (ref "R271") (pin "1") (pinfunction "1_1") (pintype "passive"))
      (node (ref "U3") (pin "N11") (pinfunction "PG5_N11") (pintype "passive"))
    )
    (net (code "295") (name "Net-(U3B-PG8)") (class "Default")
      (node (ref "R62") (pin "1") (pinfunction "1_1") (pintype "passive"))
      (node (ref "U3") (pin "H14") (pinfunction "PG8_H14") (pintype "passive"))
    )
    (net (code "296") (name "Net-(U3B-PG15)") (class "Default")
      (node (ref "R42") (pin "1") (pinfunction "1_1") (pintype "passive"))
      (node (ref "U3") (pin "B7") (pinfunction "PG15_B7") (pintype "passive"))
    )
    (net (code "297") (name "Net-(U3B-PH3)") (class "Default")
      (node (ref "R248") (pin "2") (pinfunction "2_2") (pintype "passive"))
      (node (ref "SB8") (pin "1") (pinfunction "1_1") (pintype "passive"))
      (node (ref "U3") (pin "J4") (pinfunction "PH3_J4") (pintype "passive"))
    )
    (net (code "298") (name "Net-(U3B-PH5)") (class "Default")
      (node (ref "R251") (pin "2") (pinfunction "2_2") (pintype "passive"))
      (node (ref "U3") (pin "J3") (pinfunction "PH5_J3") (pintype "passive"))
    )
    (net (code "299") (name "Net-(U3B-PH8)") (class "Default")
      (node (ref "R57") (pin "2") (pinfunction "2_2") (pintype "passive"))
      (node (ref "U3") (pin "P14") (pinfunction "PH8_P14") (pintype "passive"))
    )
    (net (code "300") (name "Net-(U3B-PH9)") (class "Default")
      (node (ref "R58") (pin "2") (pinfunction "2_2") (pintype "passive"))
      (node (ref "U3") (pin "N14") (pinfunction "PH9_N14") (pintype "passive"))
    )
    (net (code "301") (name "Net-(U3B-PH10)") (class "Default")
      (node (ref "R70") (pin "2") (pinfunction "2_2") (pintype "passive"))
      (node (ref "U3") (pin "P15") (pinfunction "PH10_P15") (pintype "passive"))
    )
    (net (code "302") (name "Net-(U3B-PH11)") (class "Default")
      (node (ref "R71") (pin "2") (pinfunction "2_2") (pintype "passive"))
      (node (ref "U3") (pin "N15") (pinfunction "PH11_N15") (pintype "passive"))
    )
    (net (code "303") (name "Net-(U3B-PH12)") (class "Default")
      (node (ref "R59") (pin "2") (pinfunction "2_2") (pintype "passive"))
      (node (ref "U3") (pin "M15") (pinfunction "PH12_M15") (pintype "passive"))
    )
    (net (code "304") (name "Net-(U3B-PH13)") (class "Default")
      (node (ref "R278") (pin "2") (pinfunction "2_2") (pintype "passive"))
      (node (ref "U3") (pin "E12") (pinfunction "PH13_E12") (pintype "passive"))
    )
    (net (code "305") (name "Net-(U3B-PH14)") (class "Default")
      (node (ref "R291") (pin "2") (pinfunction "2_2") (pintype "passive"))
      (node (ref "U3") (pin "E13") (pinfunction "PH14_E13") (pintype "passive"))
    )
    (net (code "306") (name "Net-(U3B-PH15)") (class "Default")
      (node (ref "R290") (pin "2") (pinfunction "2_2") (pintype "passive"))
      (node (ref "U3") (pin "D13") (pinfunction "PH15_D13") (pintype "passive"))
    )
    (net (code "307") (name "Net-(U3B-PI0)") (class "Default")
      (node (ref "R277") (pin "2") (pinfunction "2_2") (pintype "passive"))
      (node (ref "U3") (pin "E14") (pinfunction "PI0_E14") (pintype "passive"))
    )
    (net (code "308") (name "Net-(U3B-PI1)") (class "Default")
      (node (ref "R276") (pin "2") (pinfunction "2_2") (pintype "passive"))
      (node (ref "U3") (pin "D14") (pinfunction "PI1_D14") (pintype "passive"))
    )
    (net (code "309") (name "Net-(U3B-PI2)") (class "Default")
      (node (ref "R275") (pin "2") (pinfunction "2_2") (pintype "passive"))
      (node (ref "U3") (pin "C14") (pinfunction "PI2_C14") (pintype "passive"))
    )
    (net (code "310") (name "Net-(U3B-PI3)") (class "Default")
      (node (ref "R289") (pin "2") (pinfunction "2_2") (pintype "passive"))
      (node (ref "U3") (pin "C13") (pinfunction "PI3_C13") (pintype "passive"))
    )
    (net (code "311") (name "Net-(U3B-PI6)") (class "Default")
      (node (ref "R247") (pin "2") (pinfunction "2_2") (pintype "passive"))
      (node (ref "U3") (pin "D6") (pinfunction "PI6_D6") (pintype "passive"))
    )
    (net (code "312") (name "Net-(U3B-PI7)") (class "Default")
      (node (ref "R237") (pin "2") (pinfunction "2_2") (pintype "passive"))
      (node (ref "U3") (pin "D4") (pinfunction "PI7_D4") (pintype "passive"))
    )
    (net (code "313") (name "Net-(U3B-PI9)") (class "Default")
      (node (ref "R241") (pin "2") (pinfunction "2_2") (pintype "passive"))
      (node (ref "U3") (pin "E4") (pinfunction "PI9_E4") (pintype "passive"))
    )
    (net (code "314") (name "Net-(U3B-PI10)") (class "Default")
      (node (ref "R244") (pin "2") (pinfunction "2_2") (pintype "passive"))
      (node (ref "R43") (pin "2") (pinfunction "2_2") (pintype "passive"))
      (node (ref "U3") (pin "D5") (pinfunction "PI10_D5") (pintype "passive"))
    )
    (net (code "315") (name "Net-(U3B-PI14)") (class "Default")
      (node (ref "R295") (pin "2") (pinfunction "2_2") (pintype "passive"))
      (node (ref "U3") (pin "H3") (pinfunction "PI14_H3") (pintype "passive"))
    )
    (net (code "316") (name "Net-(U3C-BYPASS-REG)") (class "Default")
      (node (ref "R245") (pin "2") (pinfunction "2_2") (pintype "passive"))
      (node (ref "U3") (pin "L5") (pinfunction "BYPASS-REG_L5") (pintype "passive"))
    )
    (net (code "317") (name "Net-(U3C-VBAT)") (class "Default")
      (node (ref "JP8") (pin "2") (pintype "passive"))
      (node (ref "U3") (pin "C1") (pinfunction "VBAT_C1") (pintype "passive"))
    )
    (net (code "318") (name "Net-(U3C-VCAP1)") (class "Default")
      (node (ref "C133") (pin "1") (pinfunction "1_1") (pintype "passive"))
      (node (ref "U3") (pin "L11") (pinfunction "VCAP1_L11") (pintype "passive"))
    )
    (net (code "319") (name "Net-(U3C-VCAP2)") (class "Default")
      (node (ref "C32") (pin "1") (pinfunction "1_1") (pintype "passive"))
      (node (ref "U3") (pin "E11") (pinfunction "VCAP2_E11") (pintype "passive"))
    )
    (net (code "320") (name "VBUS_FS1") (class "Default")
      (node (ref "R266") (pin "2") (pinfunction "2_2") (pintype "passive"))
    )
    (net (code "321") (name "VBUS_FS2") (class "Default")
      (node (ref "R264") (pin "1") (pinfunction "1_1") (pintype "passive"))
    )
    (net (code "322") (name "VDDA") (class "Default")
      (node (ref "C108") (pin "1") (pinfunction "1_1") (pintype "passive"))
      (node (ref "C110") (pin "2") (pinfunction "2_2") (pintype "passive"))
      (node (ref "L10") (pin "2") (pinfunction "2_2") (pintype "passive"))
      (node (ref "R31") (pin "1") (pinfunction "1_1") (pintype "passive"))
      (node (ref "TP5") (pin "1") (pinfunction "1_1") (pintype "passive"))
      (node (ref "U3") (pin "R1") (pinfunction "VDDA_R1") (pintype "passive"))
    )
    (net (code "323") (name "VDD_MCU") (class "Default")
      (node (ref "C104") (pin "1") (pinfunction "1_1") (pintype "passive"))
      (node (ref "C105") (pin "1") (pinfunction "1_1") (pintype "passive"))
      (node (ref "C106") (pin "1") (pinfunction "1_1") (pintype "passive"))
      (node (ref "C109") (pin "1") (pinfunction "1_1") (pintype "passive"))
      (node (ref "C111") (pin "1") (pinfunction "1_1") (pintype "passive"))
      (node (ref "C112") (pin "1") (pinfunction "1_1") (pintype "passive"))
      (node (ref "C113") (pin "1") (pinfunction "1_1") (pintype "passive"))
      (node (ref "C114") (pin "1") (pinfunction "1_1") (pintype "passive"))
      (node (ref "C115") (pin "1") (pinfunction "1_1") (pintype "passive"))
      (node (ref "C118") (pin "1") (pinfunction "1_1") (pintype "passive"))
      (node (ref "C119") (pin "1") (pinfunction "1_1") (pintype "passive"))
      (node (ref "C120") (pin "1") (pinfunction "1_1") (pintype "passive"))
      (node (ref "C121") (pin "1") (pinfunction "1_1") (pintype "passive"))
      (node (ref "C122") (pin "1") (pinfunction "1_1") (pintype "passive"))
      (node (ref "C123") (pin "1") (pinfunction "1_1") (pintype "passive"))
      (node (ref "C125") (pin "1") (pinfunction "1_1") (pintype "passive"))
      (node (ref "C126") (pin "1") (pinfunction "1_1") (pintype "passive"))
      (node (ref "C127") (pin "1") (pinfunction "1_1") (pintype "passive"))
      (node (ref "C128") (pin "1") (pinfunction "1_1") (pintype "passive"))
      (node (ref "C129") (pin "1") (pinfunction "1_1") (pintype "passive"))
      (node (ref "C130") (pin "1") (pinfunction "1_1") (pintype "passive"))
      (node (ref "L10") (pin "1") (pinfunction "1_1") (pintype "passive"))
      (node (ref "U3") (pin "E10") (pinfunction "VDD15_E10") (pintype "passive"))
      (node (ref "U3") (pin "E7") (pinfunction "VDD3_E7") (pintype "passive"))
      (node (ref "U3") (pin "E8") (pinfunction "VDD11_E8") (pintype "passive"))
      (node (ref "U3") (pin "E9") (pinfunction "VDD10_E9") (pintype "passive"))
      (node (ref "U3") (pin "F11") (pinfunction "VDD2_F11") (pintype "passive"))
      (node (ref "U3") (pin "F4") (pinfunction "VDD13_F4") (pintype "passive"))
      (node (ref "U3") (pin "F5") (pinfunction "VDD17_F5") (pintype "passive"))
      (node (ref "U3") (pin "G11") (pinfunction "VDD9_G11") (pintype "passive"))
      (node (ref "U3") (pin "G5") (pinfunction "VDD18_G5") (pintype "passive"))
      (node (ref "U3") (pin "H11") (pinfunction "VDD20_H11") (pintype "passive"))
      (node (ref "U3") (pin "H5") (pinfunction "VDD5_H5") (pintype "passive"))
      (node (ref "U3") (pin "J11") (pinfunction "VDD8_J11") (pintype "passive"))
      (node (ref "U3") (pin "J5") (pinfunction "VDD12_J5") (pintype "passive"))
      (node (ref "U3") (pin "K11") (pinfunction "VDD14_K11") (pintype "passive"))
      (node (ref "U3") (pin "K5") (pinfunction "VDD4_K5") (pintype "passive"))
      (node (ref "U3") (pin "L10") (pinfunction "VDD1_L10") (pintype "passive"))
      (node (ref "U3") (pin "L7") (pinfunction "VDD19_L7") (pintype "passive"))
      (node (ref "U3") (pin "L8") (pinfunction "VDD6_L8") (pintype "passive"))
      (node (ref "U3") (pin "L9") (pinfunction "VDD7_L9") (pintype "passive"))
    )
    (net (code "324") (name "VREF+") (class "Default")
      (node (ref "C103") (pin "1") (pinfunction "1_1") (pintype "passive"))
      (node (ref "C107") (pin "2") (pinfunction "2_2") (pintype "passive"))
      (node (ref "R31") (pin "2") (pinfunction "2_2") (pintype "passive"))
      (node (ref "TP2") (pin "1") (pinfunction "1_1") (pintype "passive"))
      (node (ref "U3") (pin "P1") (pinfunction "VREF+_P1") (pintype "passive"))
    )
    (net (code "325") (name "unconnected-(X1-Pad2)") (class "Default")
      (node (ref "X1") (pin "2") (pinfunction "2_2") (pintype "passive+no_connect"))
    )
    (net (code "326") (name "unconnected-(X1-Pad3)") (class "Default")
      (node (ref "X1") (pin "3") (pinfunction "3_3") (pintype "passive+no_connect"))
    )
  )
)
